# axiom_beta_sensor_cmv12000_v0_14_tht_d1d.net
KiCad netlist of a schematic drawn in EAGLE
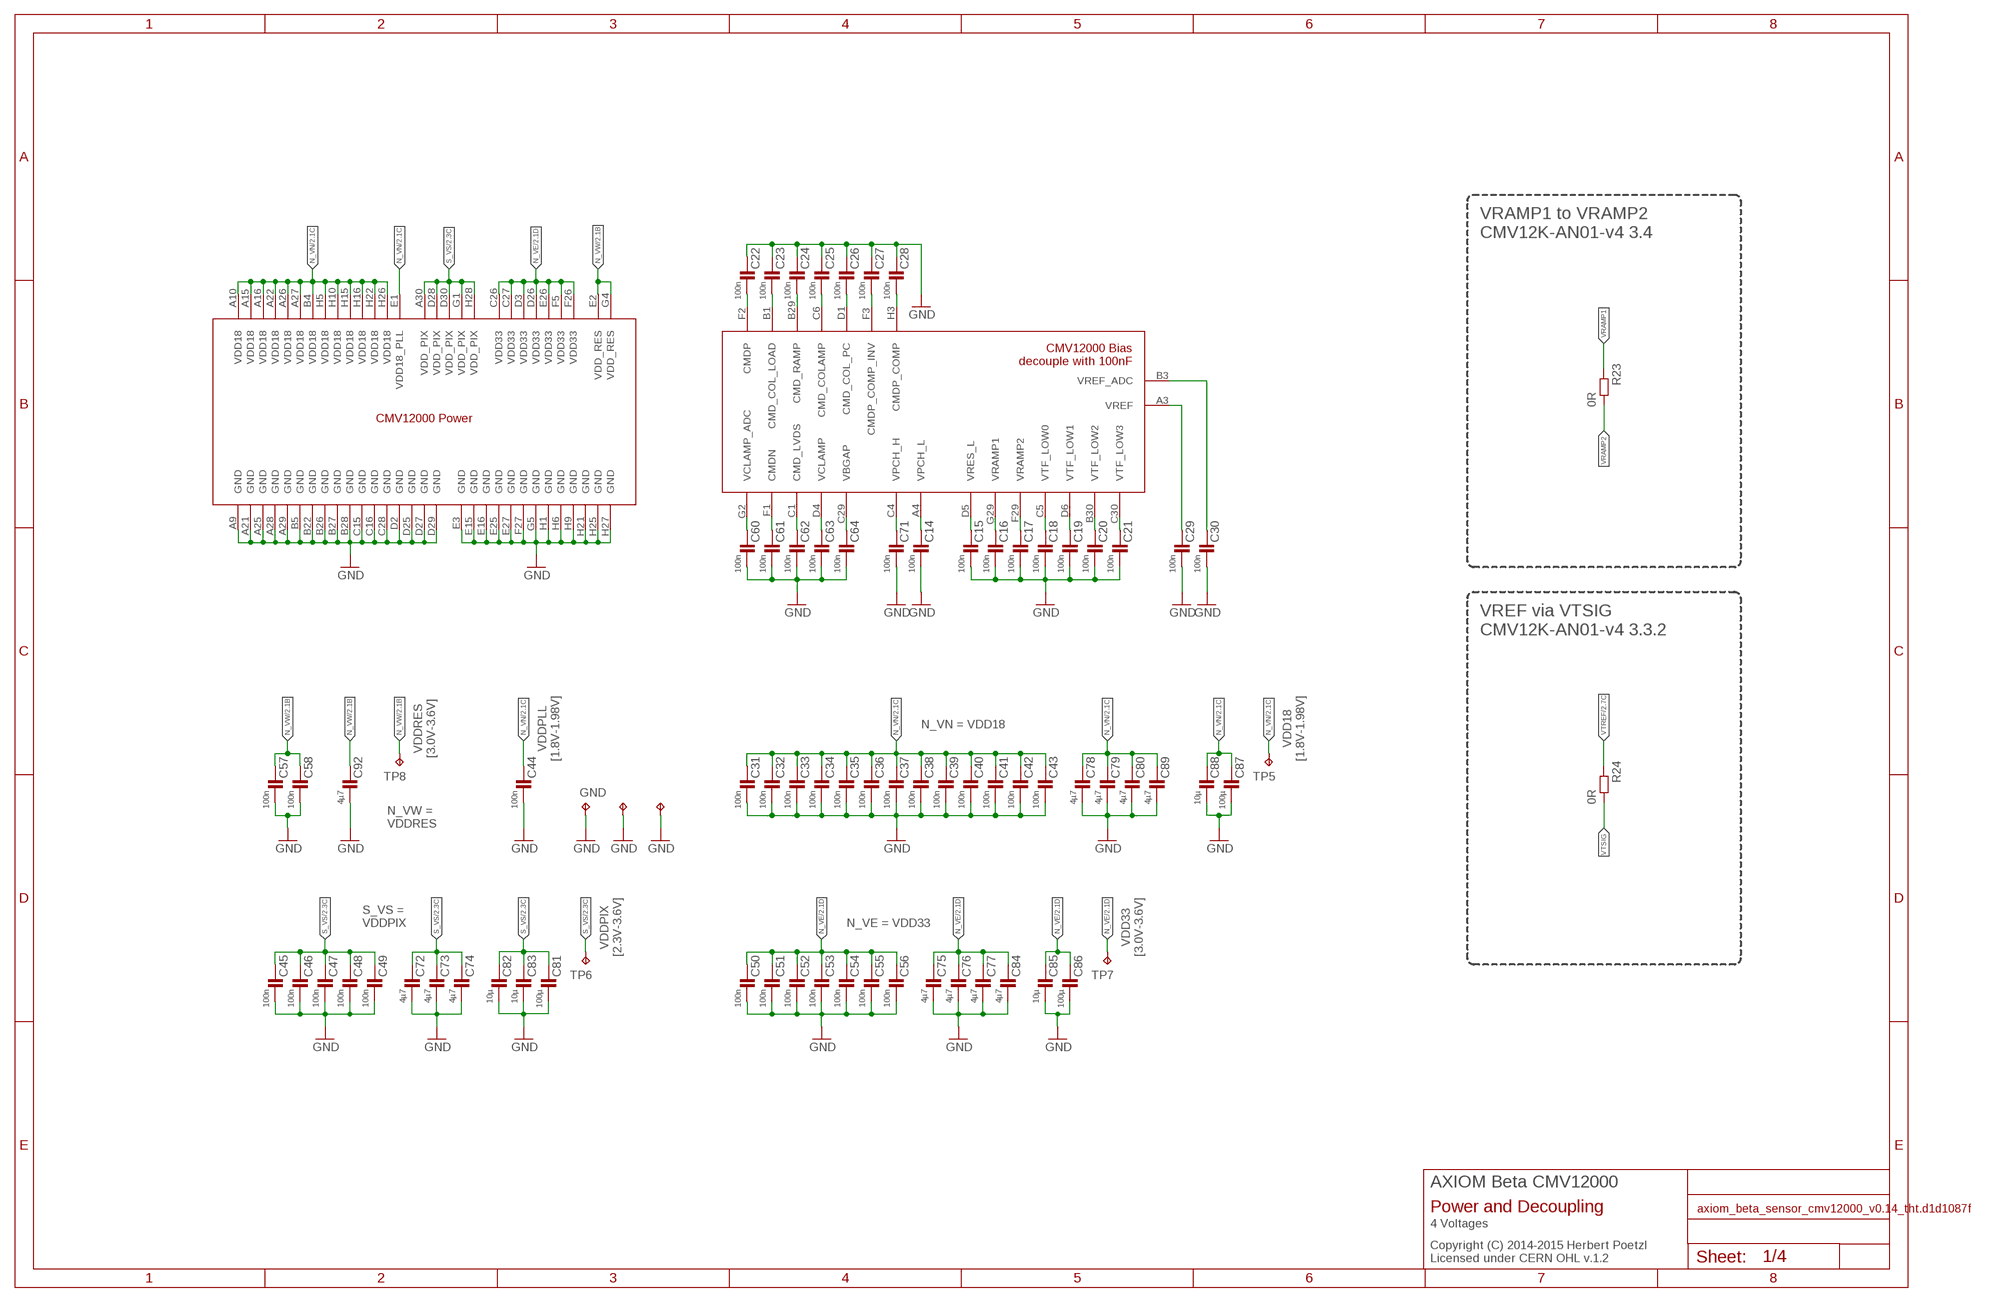
[diagram p0: schematic, sheet 1]
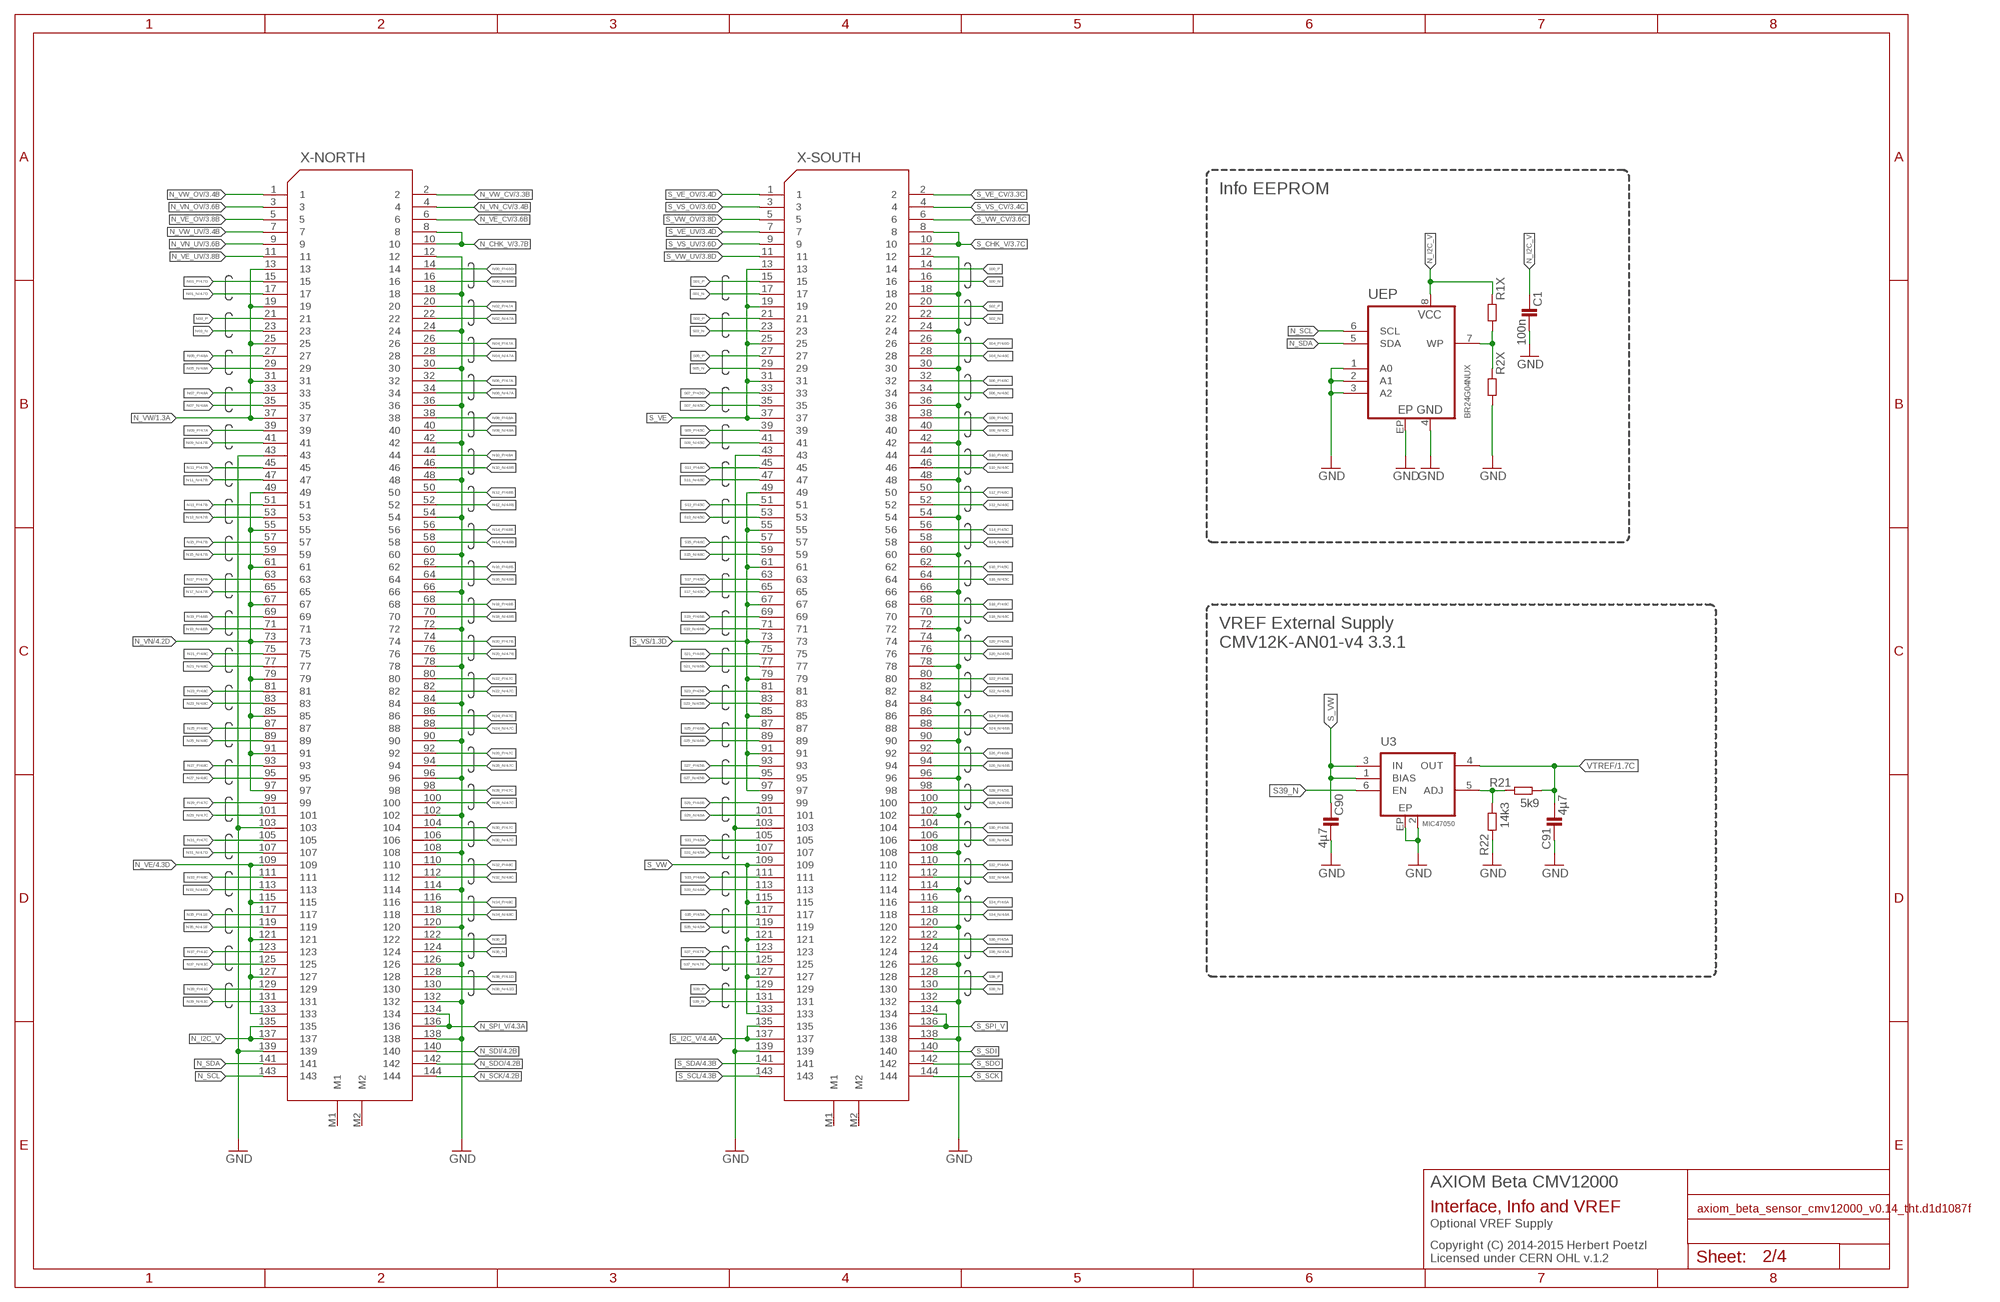
[diagram p1: schematic, sheet 2]
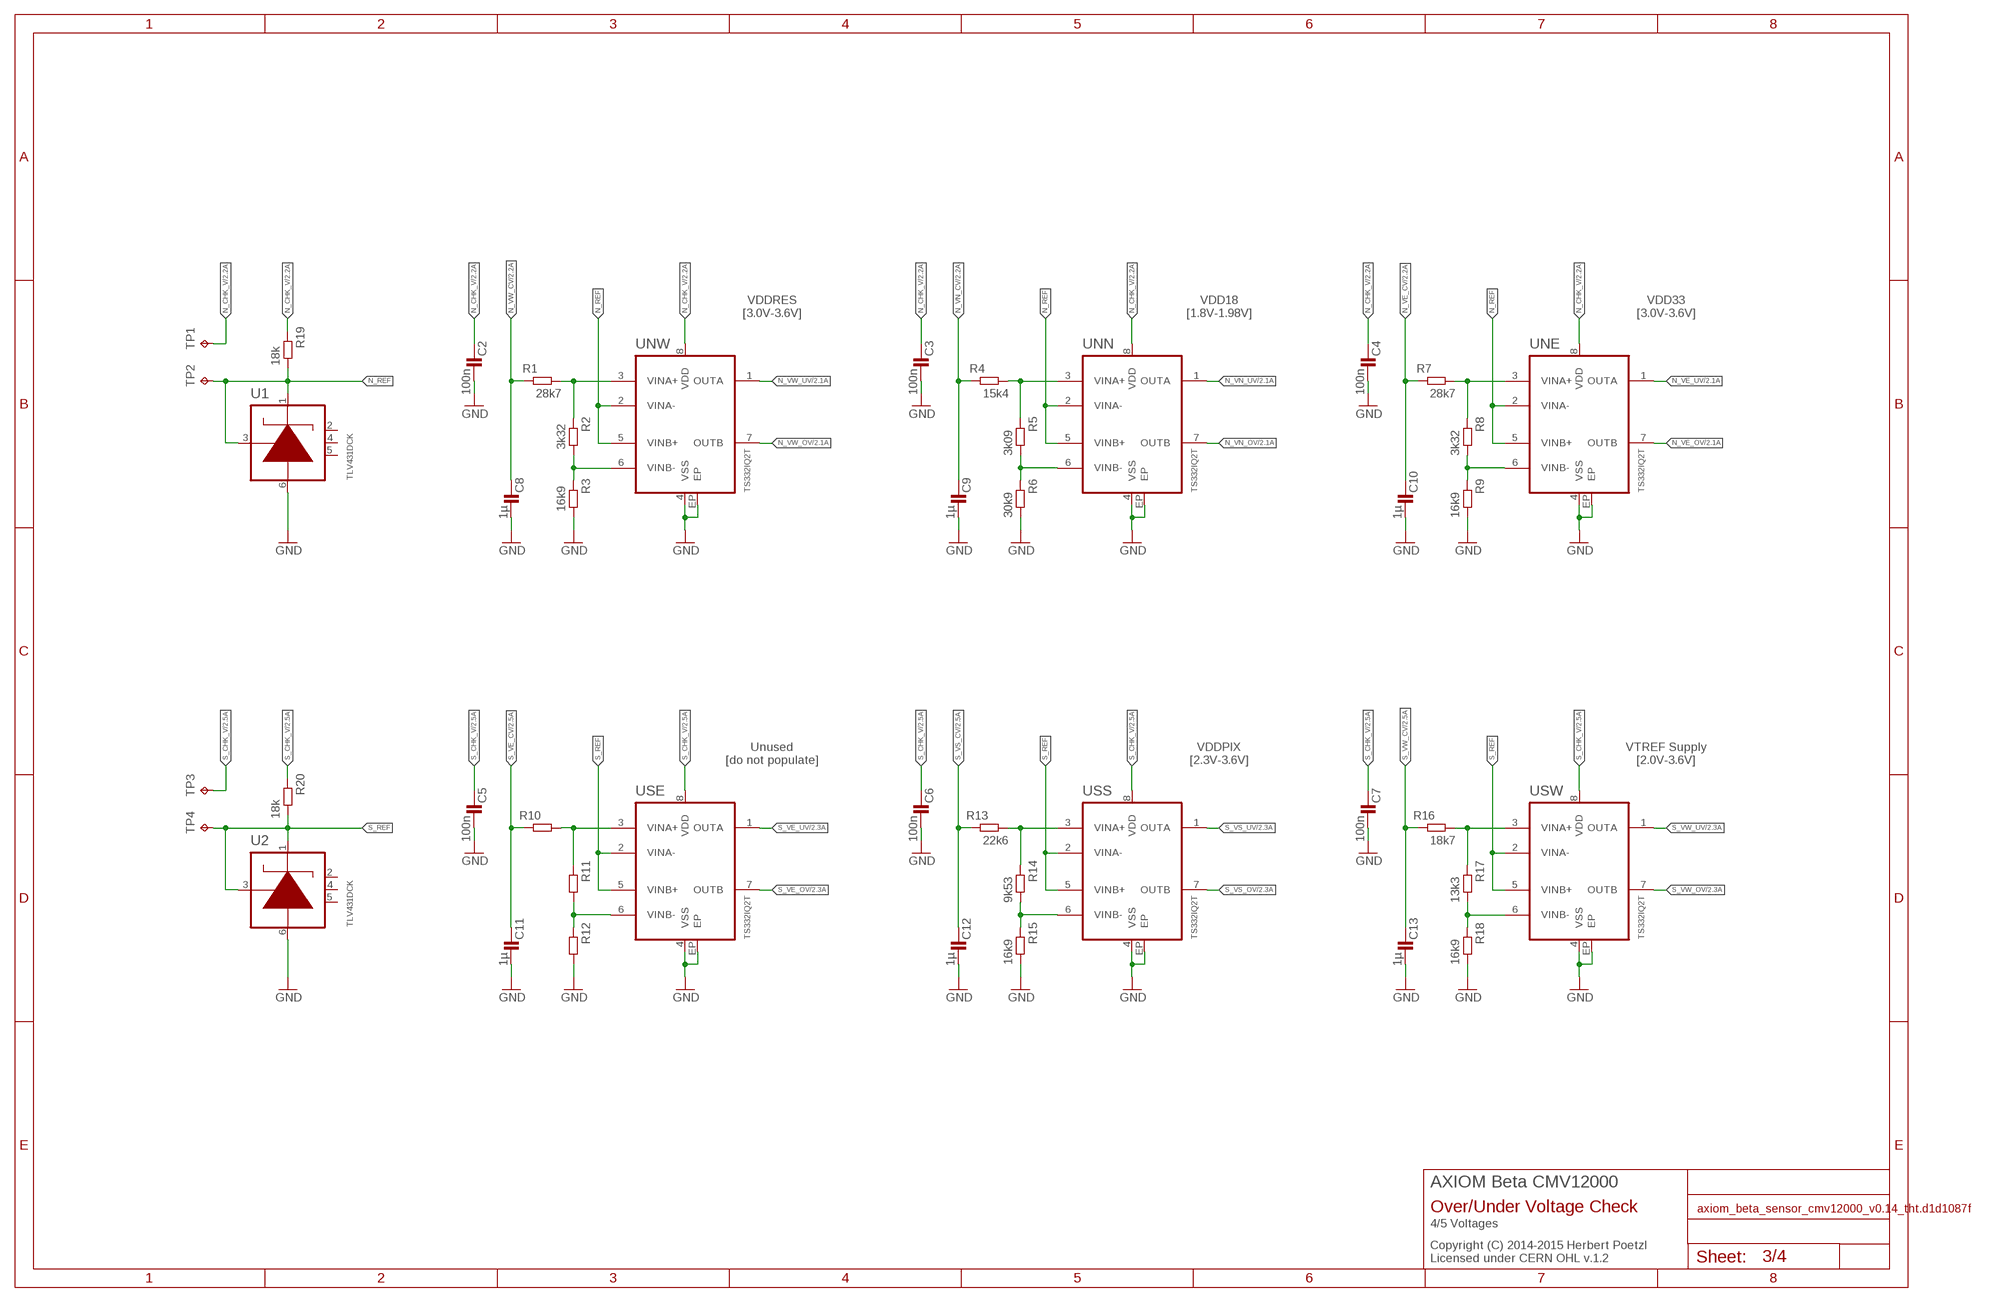
[diagram p2: schematic, sheet 3]
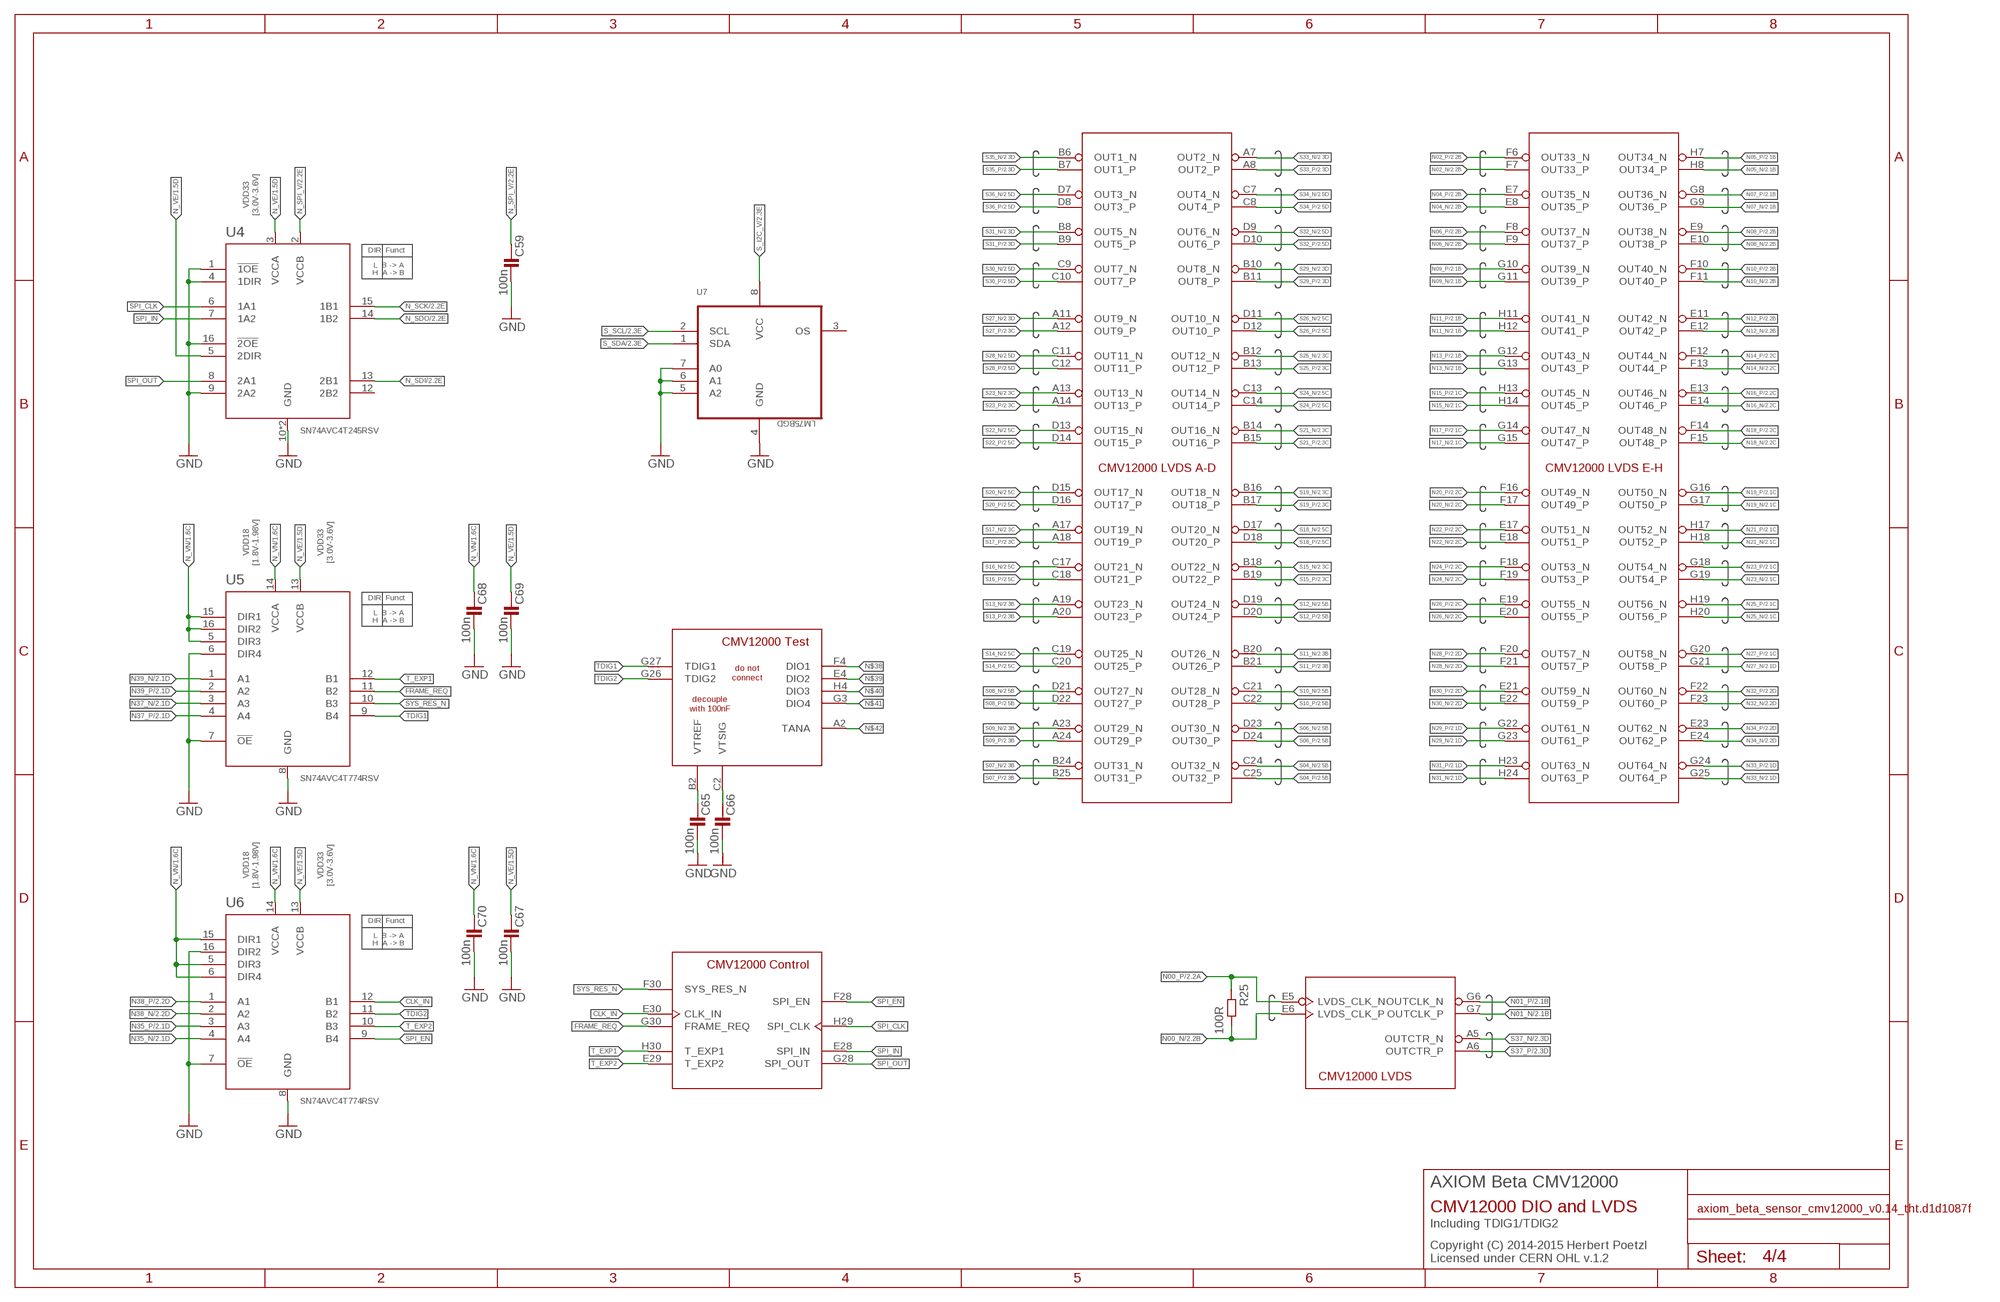
[diagram p3: schematic, sheet 4]

(export (version "E")
  (design (tool "Eeschema 10.0.6"))
  (components
    (comp (ref "C14")
      (value "100n")
      (footprint "eagle-import:0402-C")
      (libsource (lib "eagle-import") (part "C0402-C"))
    )
    (comp (ref "C15")
      (value "100n")
      (footprint "eagle-import:0402-C")
      (libsource (lib "eagle-import") (part "C0402-C"))
    )
    (comp (ref "C16")
      (value "100n")
      (footprint "eagle-import:0402-C")
      (libsource (lib "eagle-import") (part "C0402-C"))
    )
    (comp (ref "C17")
      (value "100n")
      (footprint "eagle-import:0402-C")
      (libsource (lib "eagle-import") (part "C0402-C"))
    )
    (comp (ref "C18")
      (value "100n")
      (footprint "eagle-import:0402-C")
      (libsource (lib "eagle-import") (part "C0402-C"))
    )
    (comp (ref "C19")
      (value "100n")
      (footprint "eagle-import:0402-C")
      (libsource (lib "eagle-import") (part "C0402-C"))
    )
    (comp (ref "C20")
      (value "100n")
      (footprint "eagle-import:0402-C")
      (libsource (lib "eagle-import") (part "C0402-C"))
    )
    (comp (ref "C21")
      (value "100n")
      (footprint "eagle-import:0402-C")
      (libsource (lib "eagle-import") (part "C0402-C"))
    )
    (comp (ref "C22")
      (value "100n")
      (footprint "eagle-import:0402-C")
      (libsource (lib "eagle-import") (part "C0402-C"))
    )
    (comp (ref "C23")
      (value "100n")
      (footprint "eagle-import:0402-C")
      (libsource (lib "eagle-import") (part "C0402-C"))
    )
    (comp (ref "C24")
      (value "100n")
      (footprint "eagle-import:0402-C")
      (libsource (lib "eagle-import") (part "C0402-C"))
    )
    (comp (ref "C25")
      (value "100n")
      (footprint "eagle-import:0402-C")
      (libsource (lib "eagle-import") (part "C0402-C"))
    )
    (comp (ref "C26")
      (value "100n")
      (footprint "eagle-import:0402-C")
      (libsource (lib "eagle-import") (part "C0402-C"))
    )
    (comp (ref "C27")
      (value "100n")
      (footprint "eagle-import:0402-C")
      (libsource (lib "eagle-import") (part "C0402-C"))
    )
    (comp (ref "C28")
      (value "100n")
      (footprint "eagle-import:0402-C")
      (libsource (lib "eagle-import") (part "C0402-C"))
    )
    (comp (ref "C29")
      (value "100n")
      (footprint "eagle-import:0402-C")
      (libsource (lib "eagle-import") (part "C0402-C"))
    )
    (comp (ref "C30")
      (value "100n")
      (footprint "eagle-import:0402-C")
      (libsource (lib "eagle-import") (part "C0402-C"))
    )
    (comp (ref "C31")
      (value "100n")
      (footprint "eagle-import:0402-C")
      (libsource (lib "eagle-import") (part "C0402-C"))
    )
    (comp (ref "C32")
      (value "100n")
      (footprint "eagle-import:0402-C")
      (libsource (lib "eagle-import") (part "C0402-C"))
    )
    (comp (ref "C33")
      (value "100n")
      (footprint "eagle-import:0402-C")
      (libsource (lib "eagle-import") (part "C0402-C"))
    )
    (comp (ref "C34")
      (value "100n")
      (footprint "eagle-import:0402-C")
      (libsource (lib "eagle-import") (part "C0402-C"))
    )
    (comp (ref "C35")
      (value "100n")
      (footprint "eagle-import:0402-C")
      (libsource (lib "eagle-import") (part "C0402-C"))
    )
    (comp (ref "C36")
      (value "100n")
      (footprint "eagle-import:0402-C")
      (libsource (lib "eagle-import") (part "C0402-C"))
    )
    (comp (ref "C37")
      (value "100n")
      (footprint "eagle-import:0402-C")
      (libsource (lib "eagle-import") (part "C0402-C"))
    )
    (comp (ref "C38")
      (value "100n")
      (footprint "eagle-import:0402-C")
      (libsource (lib "eagle-import") (part "C0402-C"))
    )
    (comp (ref "C39")
      (value "100n")
      (footprint "eagle-import:0402-C")
      (libsource (lib "eagle-import") (part "C0402-C"))
    )
    (comp (ref "C40")
      (value "100n")
      (footprint "eagle-import:0402-C")
      (libsource (lib "eagle-import") (part "C0402-C"))
    )
    (comp (ref "C41")
      (value "100n")
      (footprint "eagle-import:0402-C")
      (libsource (lib "eagle-import") (part "C0402-C"))
    )
    (comp (ref "C42")
      (value "100n")
      (footprint "eagle-import:0402-C")
      (libsource (lib "eagle-import") (part "C0402-C"))
    )
    (comp (ref "C43")
      (value "100n")
      (footprint "eagle-import:0402-C")
      (libsource (lib "eagle-import") (part "C0402-C"))
    )
    (comp (ref "C44")
      (value "100n")
      (footprint "eagle-import:0402-C")
      (libsource (lib "eagle-import") (part "C0402-C"))
    )
    (comp (ref "C45")
      (value "100n")
      (footprint "eagle-import:0402-C")
      (libsource (lib "eagle-import") (part "C0402-C"))
    )
    (comp (ref "C46")
      (value "100n")
      (footprint "eagle-import:0402-C")
      (libsource (lib "eagle-import") (part "C0402-C"))
    )
    (comp (ref "C47")
      (value "100n")
      (footprint "eagle-import:0402-C")
      (libsource (lib "eagle-import") (part "C0402-C"))
    )
    (comp (ref "C48")
      (value "100n")
      (footprint "eagle-import:0402-C")
      (libsource (lib "eagle-import") (part "C0402-C"))
    )
    (comp (ref "C49")
      (value "100n")
      (footprint "eagle-import:0402-C")
      (libsource (lib "eagle-import") (part "C0402-C"))
    )
    (comp (ref "C50")
      (value "100n")
      (footprint "eagle-import:0402-C")
      (libsource (lib "eagle-import") (part "C0402-C"))
    )
    (comp (ref "C51")
      (value "100n")
      (footprint "eagle-import:0402-C")
      (libsource (lib "eagle-import") (part "C0402-C"))
    )
    (comp (ref "C52")
      (value "100n")
      (footprint "eagle-import:0402-C")
      (libsource (lib "eagle-import") (part "C0402-C"))
    )
    (comp (ref "C53")
      (value "100n")
      (footprint "eagle-import:0402-C")
      (libsource (lib "eagle-import") (part "C0402-C"))
    )
    (comp (ref "C54")
      (value "100n")
      (footprint "eagle-import:0402-C")
      (libsource (lib "eagle-import") (part "C0402-C"))
    )
    (comp (ref "C55")
      (value "100n")
      (footprint "eagle-import:0402-C")
      (libsource (lib "eagle-import") (part "C0402-C"))
    )
    (comp (ref "C56")
      (value "100n")
      (footprint "eagle-import:0402-C")
      (libsource (lib "eagle-import") (part "C0402-C"))
    )
    (comp (ref "C57")
      (value "100n")
      (footprint "eagle-import:0402-C")
      (libsource (lib "eagle-import") (part "C0402-C"))
    )
    (comp (ref "C58")
      (value "100n")
      (footprint "eagle-import:0402-C")
      (libsource (lib "eagle-import") (part "C0402-C"))
    )
    (comp (ref "C60")
      (value "100n")
      (footprint "eagle-import:0402-C")
      (libsource (lib "eagle-import") (part "C0402-C"))
    )
    (comp (ref "C61")
      (value "100n")
      (footprint "eagle-import:0402-C")
      (libsource (lib "eagle-import") (part "C0402-C"))
    )
    (comp (ref "C62")
      (value "100n")
      (footprint "eagle-import:0402-C")
      (libsource (lib "eagle-import") (part "C0402-C"))
    )
    (comp (ref "C63")
      (value "100n")
      (footprint "eagle-import:0402-C")
      (libsource (lib "eagle-import") (part "C0402-C"))
    )
    (comp (ref "C64")
      (value "100n")
      (footprint "eagle-import:0402-C")
      (libsource (lib "eagle-import") (part "C0402-C"))
    )
    (comp (ref "C71")
      (value "100n")
      (footprint "eagle-import:0402-C")
      (libsource (lib "eagle-import") (part "C0402-C"))
    )
    (comp (ref "C72")
      (value "4µ7")
      (footprint "eagle-import:0402-B")
      (libsource (lib "eagle-import") (part "C0402-B"))
    )
    (comp (ref "C73")
      (value "4µ7")
      (footprint "eagle-import:0402-C")
      (libsource (lib "eagle-import") (part "C0402-C"))
    )
    (comp (ref "C74")
      (value "4µ7")
      (footprint "eagle-import:0402-C")
      (libsource (lib "eagle-import") (part "C0402-C"))
    )
    (comp (ref "C75")
      (value "4µ7")
      (footprint "eagle-import:0402-C")
      (libsource (lib "eagle-import") (part "C0402-C"))
    )
    (comp (ref "C76")
      (value "4µ7")
      (footprint "eagle-import:0402-C")
      (libsource (lib "eagle-import") (part "C0402-C"))
    )
    (comp (ref "C77")
      (value "4µ7")
      (footprint "eagle-import:0402-B")
      (libsource (lib "eagle-import") (part "C0402-B"))
    )
    (comp (ref "C78")
      (value "4µ7")
      (footprint "eagle-import:0402-B")
      (libsource (lib "eagle-import") (part "C0402-B"))
    )
    (comp (ref "C79")
      (value "4µ7")
      (footprint "eagle-import:0402-C")
      (libsource (lib "eagle-import") (part "C0402-C"))
    )
    (comp (ref "C80")
      (value "4µ7")
      (footprint "eagle-import:0402-C")
      (libsource (lib "eagle-import") (part "C0402-C"))
    )
    (comp (ref "C81")
      (value "100µ")
      (footprint "eagle-import:1206-B")
      (libsource (lib "eagle-import") (part "C1206-B"))
    )
    (comp (ref "C82")
      (value "10µ")
      (footprint "eagle-import:0603-C")
      (libsource (lib "eagle-import") (part "C0603-C"))
    )
    (comp (ref "C83")
      (value "10µ")
      (footprint "eagle-import:0603-C")
      (libsource (lib "eagle-import") (part "C0603-C"))
    )
    (comp (ref "C84")
      (value "4µ7")
      (footprint "eagle-import:0402-C")
      (libsource (lib "eagle-import") (part "C0402-C"))
    )
    (comp (ref "C85")
      (value "10µ")
      (footprint "eagle-import:0603-C")
      (libsource (lib "eagle-import") (part "C0603-C"))
    )
    (comp (ref "C86")
      (value "100µ")
      (footprint "eagle-import:1206-B")
      (libsource (lib "eagle-import") (part "C1206-B"))
    )
    (comp (ref "C87")
      (value "100µ")
      (footprint "eagle-import:1206-B")
      (libsource (lib "eagle-import") (part "C1206-B"))
    )
    (comp (ref "C88")
      (value "10µ")
      (footprint "eagle-import:0603-C")
      (libsource (lib "eagle-import") (part "C0603-C"))
    )
    (comp (ref "C89")
      (value "4µ7")
      (footprint "eagle-import:0402-C")
      (libsource (lib "eagle-import") (part "C0402-C"))
    )
    (comp (ref "C92")
      (value "4µ7")
      (footprint "eagle-import:0402-C")
      (libsource (lib "eagle-import") (part "C0402-C"))
    )
    (comp (ref "GND")
      (value "TPTP10R")
      (footprint "eagle-import:TP10R")
      (libsource (lib "eagle-import") (part "TPTP10R"))
    )
    (comp (ref "GND75")
      (value "TPTP10R")
      (footprint "eagle-import:TP10R")
      (libsource (lib "eagle-import") (part "TPTP10R"))
    )
    (comp (ref "GND77")
      (value "TPTP10R")
      (footprint "eagle-import:TP10R")
      (libsource (lib "eagle-import") (part "TPTP10R"))
    )
    (comp (ref "R23")
      (value "0R")
      (footprint "eagle-import:0402-C")
      (libsource (lib "eagle-import") (part "R0402-C"))
    )
    (comp (ref "R24")
      (value "0R")
      (footprint "eagle-import:0402-C")
      (libsource (lib "eagle-import") (part "R0402-C"))
    )
    (comp (ref "SENSOR")
      (value "CMV12000ANDON")
      (footprint "eagle-import:10-30-07-237-400T4")
      (libsource (lib "eagle-import") (part "CMV12000ANDON"))
    )
    (comp (ref "TP5")
      (value "TPTP10R")
      (footprint "eagle-import:TP10R")
      (libsource (lib "eagle-import") (part "TPTP10R"))
    )
    (comp (ref "TP6")
      (value "TPTP10R")
      (footprint "eagle-import:TP10R")
      (libsource (lib "eagle-import") (part "TPTP10R"))
    )
    (comp (ref "TP7")
      (value "TPTP10R")
      (footprint "eagle-import:TP10R")
      (libsource (lib "eagle-import") (part "TPTP10R"))
    )
    (comp (ref "TP8")
      (value "TPTP10R")
      (footprint "eagle-import:TP10R")
      (libsource (lib "eagle-import") (part "TPTP10R"))
    )
    (comp (ref "C59")
      (value "100n")
      (footprint "eagle-import:0402-C")
      (libsource (lib "eagle-import") (part "C0402-C"))
    )
    (comp (ref "C65")
      (value "100n")
      (footprint "eagle-import:0402-C")
      (libsource (lib "eagle-import") (part "C0402-C"))
    )
    (comp (ref "C66")
      (value "100n")
      (footprint "eagle-import:0402-C")
      (libsource (lib "eagle-import") (part "C0402-C"))
    )
    (comp (ref "C67")
      (value "100n")
      (footprint "eagle-import:0402-C")
      (libsource (lib "eagle-import") (part "C0402-C"))
    )
    (comp (ref "C68")
      (value "100n")
      (footprint "eagle-import:0402-C")
      (libsource (lib "eagle-import") (part "C0402-C"))
    )
    (comp (ref "C69")
      (value "100n")
      (footprint "eagle-import:0402-C")
      (libsource (lib "eagle-import") (part "C0402-C"))
    )
    (comp (ref "C70")
      (value "100n")
      (footprint "eagle-import:0402-C")
      (libsource (lib "eagle-import") (part "C0402-C"))
    )
    (comp (ref "R25")
      (value "100R")
      (footprint "eagle-import:0402-C")
      (libsource (lib "eagle-import") (part "R0402-C"))
    )
    (comp (ref "U4")
      (value "SN74AVC4T245RSV")
      (footprint "eagle-import:QFN40P185X265X55-16N")
      (libsource (lib "eagle-import") (part "SN74AVC4T245RSV"))
    )
    (comp (ref "U5")
      (value "SN74AVC4T774RSV")
      (footprint "eagle-import:QFN40P185X265X55-16N")
      (libsource (lib "eagle-import") (part "SN74AVC4T774RSV"))
    )
    (comp (ref "U6")
      (value "SN74AVC4T774RSV")
      (footprint "eagle-import:QFN40P185X265X55-16N")
      (libsource (lib "eagle-import") (part "SN74AVC4T774RSV"))
    )
    (comp (ref "U7")
      (value "LM75BGD")
      (footprint "eagle-import:SOT996-2_3")
      (libsource (lib "eagle-import") (part "LM75BGD"))
    )
    (comp (ref "C1")
      (value "100n")
      (footprint "eagle-import:0402-C")
      (libsource (lib "eagle-import") (part "C0402-C"))
    )
    (comp (ref "C90")
      (value "4µ7")
      (footprint "eagle-import:0402-C")
      (libsource (lib "eagle-import") (part "C0402-C"))
    )
    (comp (ref "C91")
      (value "4µ7")
      (footprint "eagle-import:0402-C")
      (libsource (lib "eagle-import") (part "C0402-C"))
    )
    (comp (ref "R1X")
      (value "R0402-C")
      (footprint "eagle-import:0402-C")
      (libsource (lib "eagle-import") (part "R0402-C"))
    )
    (comp (ref "R2X")
      (value "R0402-C")
      (footprint "eagle-import:0402-C")
      (libsource (lib "eagle-import") (part "R0402-C"))
    )
    (comp (ref "R21")
      (value "5k9")
      (footprint "eagle-import:0402-C")
      (libsource (lib "eagle-import") (part "R0402-C"))
    )
    (comp (ref "R22")
      (value "14k3")
      (footprint "eagle-import:0402-C")
      (libsource (lib "eagle-import") (part "R0402-C"))
    )
    (comp (ref "U3")
      (value "MIC47050")
      (footprint "eagle-import:MLF-6")
      (libsource (lib "eagle-import") (part "MIC47050-ADJ"))
    )
    (comp (ref "UEP")
      (value "BR24G04NUX")
      (footprint "eagle-import:DFN200X300X100-9N")
      (libsource (lib "eagle-import") (part "BR24G04NUX"))
    )
    (comp (ref "X-NORTH")
      (value "FX10-144P")
      (footprint "eagle-import:FX10A-144P")
      (libsource (lib "eagle-import") (part "FX10-144P"))
    )
    (comp (ref "X-SOUTH")
      (value "FX10-144P")
      (footprint "eagle-import:FX10A-144P")
      (libsource (lib "eagle-import") (part "FX10-144P"))
    )
    (comp (ref "C2")
      (value "100n")
      (footprint "eagle-import:0402-C")
      (libsource (lib "eagle-import") (part "C0402-C"))
    )
    (comp (ref "C3")
      (value "100n")
      (footprint "eagle-import:0402-C")
      (libsource (lib "eagle-import") (part "C0402-C"))
    )
    (comp (ref "C4")
      (value "100n")
      (footprint "eagle-import:0402-C")
      (libsource (lib "eagle-import") (part "C0402-C"))
    )
    (comp (ref "C5")
      (value "100n")
      (footprint "eagle-import:0402-C")
      (libsource (lib "eagle-import") (part "C0402-C"))
    )
    (comp (ref "C6")
      (value "100n")
      (footprint "eagle-import:0402-C")
      (libsource (lib "eagle-import") (part "C0402-C"))
    )
    (comp (ref "C7")
      (value "100n")
      (footprint "eagle-import:0402-C")
      (libsource (lib "eagle-import") (part "C0402-C"))
    )
    (comp (ref "C8")
      (value "1µ")
      (footprint "eagle-import:0402-C")
      (libsource (lib "eagle-import") (part "C0402-C"))
    )
    (comp (ref "C9")
      (value "1µ")
      (footprint "eagle-import:0402-C")
      (libsource (lib "eagle-import") (part "C0402-C"))
    )
    (comp (ref "C10")
      (value "1µ")
      (footprint "eagle-import:0402-C")
      (libsource (lib "eagle-import") (part "C0402-C"))
    )
    (comp (ref "C11")
      (value "1µ")
      (footprint "eagle-import:0402-C")
      (libsource (lib "eagle-import") (part "C0402-C"))
    )
    (comp (ref "C12")
      (value "1µ")
      (footprint "eagle-import:0402-C")
      (libsource (lib "eagle-import") (part "C0402-C"))
    )
    (comp (ref "C13")
      (value "1µ")
      (footprint "eagle-import:0402-C")
      (libsource (lib "eagle-import") (part "C0402-C"))
    )
    (comp (ref "R1")
      (value "28k7")
      (footprint "eagle-import:0402-C")
      (libsource (lib "eagle-import") (part "R0402-C"))
    )
    (comp (ref "R2")
      (value "3k32")
      (footprint "eagle-import:0402-C")
      (libsource (lib "eagle-import") (part "R0402-C"))
    )
    (comp (ref "R3")
      (value "16k9")
      (footprint "eagle-import:0402-C")
      (libsource (lib "eagle-import") (part "R0402-C"))
    )
    (comp (ref "R4")
      (value "15k4")
      (footprint "eagle-import:0402-C")
      (libsource (lib "eagle-import") (part "R0402-C"))
    )
    (comp (ref "R5")
      (value "3k09")
      (footprint "eagle-import:0402-C")
      (libsource (lib "eagle-import") (part "R0402-C"))
    )
    (comp (ref "R6")
      (value "30k9")
      (footprint "eagle-import:0402-C")
      (libsource (lib "eagle-import") (part "R0402-C"))
    )
    (comp (ref "R7")
      (value "28k7")
      (footprint "eagle-import:0402-C")
      (libsource (lib "eagle-import") (part "R0402-C"))
    )
    (comp (ref "R8")
      (value "3k32")
      (footprint "eagle-import:0402-C")
      (libsource (lib "eagle-import") (part "R0402-C"))
    )
    (comp (ref "R9")
      (value "16k9")
      (footprint "eagle-import:0402-C")
      (libsource (lib "eagle-import") (part "R0402-C"))
    )
    (comp (ref "R10")
      (value "R0402-C")
      (footprint "eagle-import:0402-C")
      (libsource (lib "eagle-import") (part "R0402-C"))
    )
    (comp (ref "R11")
      (value "R0402-C")
      (footprint "eagle-import:0402-C")
      (libsource (lib "eagle-import") (part "R0402-C"))
    )
    (comp (ref "R12")
      (value "R0402-C")
      (footprint "eagle-import:0402-C")
      (libsource (lib "eagle-import") (part "R0402-C"))
    )
    (comp (ref "R13")
      (value "22k6")
      (footprint "eagle-import:0402-C")
      (libsource (lib "eagle-import") (part "R0402-C"))
    )
    (comp (ref "R14")
      (value "9k53")
      (footprint "eagle-import:0402-C")
      (libsource (lib "eagle-import") (part "R0402-C"))
    )
    (comp (ref "R15")
      (value "16k9")
      (footprint "eagle-import:0402-C")
      (libsource (lib "eagle-import") (part "R0402-C"))
    )
    (comp (ref "R16")
      (value "18k7")
      (footprint "eagle-import:0402-C")
      (libsource (lib "eagle-import") (part "R0402-C"))
    )
    (comp (ref "R17")
      (value "13k3")
      (footprint "eagle-import:0402-C")
      (libsource (lib "eagle-import") (part "R0402-C"))
    )
    (comp (ref "R18")
      (value "16k9")
      (footprint "eagle-import:0402-C")
      (libsource (lib "eagle-import") (part "R0402-C"))
    )
    (comp (ref "R19")
      (value "18k")
      (footprint "eagle-import:0402-C")
      (libsource (lib "eagle-import") (part "R0402-C"))
    )
    (comp (ref "R20")
      (value "18k")
      (footprint "eagle-import:0402-C")
      (libsource (lib "eagle-import") (part "R0402-C"))
    )
    (comp (ref "TP1")
      (value "TPTP10R")
      (footprint "eagle-import:TP10R")
      (libsource (lib "eagle-import") (part "TPTP10R"))
    )
    (comp (ref "TP2")
      (value "TPTP10R")
      (footprint "eagle-import:TP10R")
      (libsource (lib "eagle-import") (part "TPTP10R"))
    )
    (comp (ref "TP3")
      (value "TPTP10R")
      (footprint "eagle-import:TP10R")
      (libsource (lib "eagle-import") (part "TPTP10R"))
    )
    (comp (ref "TP4")
      (value "TPTP10R")
      (footprint "eagle-import:TP10R")
      (libsource (lib "eagle-import") (part "TPTP10R"))
    )
    (comp (ref "U1")
      (value "TLV431DCK")
      (footprint "eagle-import:SOT65P210X110-6N")
      (libsource (lib "eagle-import") (part "TLV431DCK"))
    )
    (comp (ref "U2")
      (value "TLV431DCK")
      (footprint "eagle-import:SOT65P210X110-6N")
      (libsource (lib "eagle-import") (part "TLV431DCK"))
    )
    (comp (ref "UNE")
      (value "TS332IQ2T")
      (footprint "eagle-import:DFN200X200X100-9N")
      (libsource (lib "eagle-import") (part "TS332IQ2T"))
    )
    (comp (ref "UNN")
      (value "TS332IQ2T")
      (footprint "eagle-import:DFN200X200X100-9N")
      (libsource (lib "eagle-import") (part "TS332IQ2T"))
    )
    (comp (ref "UNW")
      (value "TS332IQ2T")
      (footprint "eagle-import:DFN200X200X100-9N")
      (libsource (lib "eagle-import") (part "TS332IQ2T"))
    )
    (comp (ref "USE")
      (value "TS332IQ2T")
      (footprint "eagle-import:DFN200X200X100-9N")
      (libsource (lib "eagle-import") (part "TS332IQ2T"))
    )
    (comp (ref "USS")
      (value "TS332IQ2T")
      (footprint "eagle-import:DFN200X200X100-9N")
      (libsource (lib "eagle-import") (part "TS332IQ2T"))
    )
    (comp (ref "USW")
      (value "TS332IQ2T")
      (footprint "eagle-import:DFN200X200X100-9N")
      (libsource (lib "eagle-import") (part "TS332IQ2T"))
    )
  )
  (nets
    (net (code "1") (name "CLK_IN") (class "Default")
      (node (ref "SENSOR") (pin "E30") (pinfunction "CLK_IN_E30") (pintype "input"))
      (node (ref "U6") (pin "12") (pinfunction "B1_12") (pintype "bidirectional"))
    )
    (net (code "2") (name "FRAME_REQ") (class "Default")
      (node (ref "SENSOR") (pin "G30") (pinfunction "FRAME_REQ_G30") (pintype "input"))
      (node (ref "U5") (pin "11") (pinfunction "B2_11") (pintype "bidirectional"))
    )
    (net (code "3") (name "GND") (class "Default")
      (node (ref "C1") (pin "2") (pinfunction "2_2") (pintype "passive"))
      (node (ref "C10") (pin "2") (pinfunction "2_2") (pintype "passive"))
      (node (ref "C11") (pin "2") (pinfunction "2_2") (pintype "passive"))
      (node (ref "C12") (pin "2") (pinfunction "2_2") (pintype "passive"))
      (node (ref "C13") (pin "2") (pinfunction "2_2") (pintype "passive"))
      (node (ref "C14") (pin "2") (pinfunction "2_2") (pintype "passive"))
      (node (ref "C15") (pin "2") (pinfunction "2_2") (pintype "passive"))
      (node (ref "C16") (pin "2") (pinfunction "2_2") (pintype "passive"))
      (node (ref "C17") (pin "2") (pinfunction "2_2") (pintype "passive"))
      (node (ref "C18") (pin "2") (pinfunction "2_2") (pintype "passive"))
      (node (ref "C19") (pin "2") (pinfunction "2_2") (pintype "passive"))
      (node (ref "C2") (pin "2") (pinfunction "2_2") (pintype "passive"))
      (node (ref "C20") (pin "2") (pinfunction "2_2") (pintype "passive"))
      (node (ref "C21") (pin "2") (pinfunction "2_2") (pintype "passive"))
      (node (ref "C22") (pin "1") (pinfunction "1_1") (pintype "passive"))
      (node (ref "C23") (pin "1") (pinfunction "1_1") (pintype "passive"))
      (node (ref "C24") (pin "1") (pinfunction "1_1") (pintype "passive"))
      (node (ref "C25") (pin "1") (pinfunction "1_1") (pintype "passive"))
      (node (ref "C26") (pin "1") (pinfunction "1_1") (pintype "passive"))
      (node (ref "C27") (pin "1") (pinfunction "1_1") (pintype "passive"))
      (node (ref "C28") (pin "1") (pinfunction "1_1") (pintype "passive"))
      (node (ref "C29") (pin "2") (pinfunction "2_2") (pintype "passive"))
      (node (ref "C3") (pin "2") (pinfunction "2_2") (pintype "passive"))
      (node (ref "C30") (pin "2") (pinfunction "2_2") (pintype "passive"))
      (node (ref "C31") (pin "2") (pinfunction "2_2") (pintype "passive"))
      (node (ref "C32") (pin "2") (pinfunction "2_2") (pintype "passive"))
      (node (ref "C33") (pin "2") (pinfunction "2_2") (pintype "passive"))
      (node (ref "C34") (pin "2") (pinfunction "2_2") (pintype "passive"))
      (node (ref "C35") (pin "2") (pinfunction "2_2") (pintype "passive"))
      (node (ref "C36") (pin "2") (pinfunction "2_2") (pintype "passive"))
      (node (ref "C37") (pin "2") (pinfunction "2_2") (pintype "passive"))
      (node (ref "C38") (pin "2") (pinfunction "2_2") (pintype "passive"))
      (node (ref "C39") (pin "2") (pinfunction "2_2") (pintype "passive"))
      (node (ref "C4") (pin "2") (pinfunction "2_2") (pintype "passive"))
      (node (ref "C40") (pin "2") (pinfunction "2_2") (pintype "passive"))
      (node (ref "C41") (pin "2") (pinfunction "2_2") (pintype "passive"))
      (node (ref "C42") (pin "2") (pinfunction "2_2") (pintype "passive"))
      (node (ref "C43") (pin "2") (pinfunction "2_2") (pintype "passive"))
      (node (ref "C44") (pin "2") (pinfunction "2_2") (pintype "passive"))
      (node (ref "C45") (pin "2") (pinfunction "2_2") (pintype "passive"))
      (node (ref "C46") (pin "2") (pinfunction "2_2") (pintype "passive"))
      (node (ref "C47") (pin "2") (pinfunction "2_2") (pintype "passive"))
      (node (ref "C48") (pin "2") (pinfunction "2_2") (pintype "passive"))
      (node (ref "C49") (pin "2") (pinfunction "2_2") (pintype "passive"))
      (node (ref "C5") (pin "2") (pinfunction "2_2") (pintype "passive"))
      (node (ref "C50") (pin "2") (pinfunction "2_2") (pintype "passive"))
      (node (ref "C51") (pin "2") (pinfunction "2_2") (pintype "passive"))
      (node (ref "C52") (pin "2") (pinfunction "2_2") (pintype "passive"))
      (node (ref "C53") (pin "2") (pinfunction "2_2") (pintype "passive"))
      (node (ref "C54") (pin "2") (pinfunction "2_2") (pintype "passive"))
      (node (ref "C55") (pin "2") (pinfunction "2_2") (pintype "passive"))
      (node (ref "C56") (pin "2") (pinfunction "2_2") (pintype "passive"))
      (node (ref "C57") (pin "2") (pinfunction "2_2") (pintype "passive"))
      (node (ref "C58") (pin "2") (pinfunction "2_2") (pintype "passive"))
      (node (ref "C59") (pin "2") (pinfunction "2_2") (pintype "passive"))
      (node (ref "C6") (pin "2") (pinfunction "2_2") (pintype "passive"))
      (node (ref "C60") (pin "2") (pinfunction "2_2") (pintype "passive"))
      (node (ref "C61") (pin "2") (pinfunction "2_2") (pintype "passive"))
      (node (ref "C62") (pin "2") (pinfunction "2_2") (pintype "passive"))
      (node (ref "C63") (pin "2") (pinfunction "2_2") (pintype "passive"))
      (node (ref "C64") (pin "2") (pinfunction "2_2") (pintype "passive"))
      (node (ref "C65") (pin "2") (pinfunction "2_2") (pintype "passive"))
      (node (ref "C66") (pin "2") (pinfunction "2_2") (pintype "passive"))
      (node (ref "C67") (pin "2") (pinfunction "2_2") (pintype "passive"))
      (node (ref "C68") (pin "2") (pinfunction "2_2") (pintype "passive"))
      (node (ref "C69") (pin "2") (pinfunction "2_2") (pintype "passive"))
      (node (ref "C7") (pin "2") (pinfunction "2_2") (pintype "passive"))
      (node (ref "C70") (pin "2") (pinfunction "2_2") (pintype "passive"))
      (node (ref "C71") (pin "2") (pinfunction "2_2") (pintype "passive"))
      (node (ref "C72") (pin "2") (pinfunction "2_2") (pintype "passive"))
      (node (ref "C73") (pin "2") (pinfunction "2_2") (pintype "passive"))
      (node (ref "C74") (pin "2") (pinfunction "2_2") (pintype "passive"))
      (node (ref "C75") (pin "2") (pinfunction "2_2") (pintype "passive"))
      (node (ref "C76") (pin "2") (pinfunction "2_2") (pintype "passive"))
      (node (ref "C77") (pin "2") (pinfunction "2_2") (pintype "passive"))
      (node (ref "C78") (pin "2") (pinfunction "2_2") (pintype "passive"))
      (node (ref "C79") (pin "2") (pinfunction "2_2") (pintype "passive"))
      (node (ref "C8") (pin "2") (pinfunction "2_2") (pintype "passive"))
      (node (ref "C80") (pin "2") (pinfunction "2_2") (pintype "passive"))
      (node (ref "C81") (pin "2") (pinfunction "2_2") (pintype "passive"))
      (node (ref "C82") (pin "2") (pinfunction "2_2") (pintype "passive"))
      (node (ref "C83") (pin "2") (pinfunction "2_2") (pintype "passive"))
      (node (ref "C84") (pin "2") (pinfunction "2_2") (pintype "passive"))
      (node (ref "C85") (pin "2") (pinfunction "2_2") (pintype "passive"))
      (node (ref "C86") (pin "2") (pinfunction "2_2") (pintype "passive"))
      (node (ref "C87") (pin "2") (pinfunction "2_2") (pintype "passive"))
      (node (ref "C88") (pin "2") (pinfunction "2_2") (pintype "passive"))
      (node (ref "C89") (pin "2") (pinfunction "2_2") (pintype "passive"))
      (node (ref "C9") (pin "2") (pinfunction "2_2") (pintype "passive"))
      (node (ref "C90") (pin "2") (pinfunction "2_2") (pintype "passive"))
      (node (ref "C91") (pin "1") (pinfunction "1_1") (pintype "passive"))
      (node (ref "C92") (pin "2") (pinfunction "2_2") (pintype "passive"))
      (node (ref "GND") (pin "TP") (pinfunction "TP_TP") (pintype "input"))
      (node (ref "GND75") (pin "TP") (pinfunction "TP_TP") (pintype "input"))
      (node (ref "GND77") (pin "TP") (pinfunction "TP_TP") (pintype "input"))
      (node (ref "R12") (pin "2") (pinfunction "2_2") (pintype "passive"))
      (node (ref "R15") (pin "2") (pinfunction "2_2") (pintype "passive"))
      (node (ref "R18") (pin "2") (pinfunction "2_2") (pintype "passive"))
      (node (ref "R22") (pin "1") (pinfunction "1_1") (pintype "passive"))
      (node (ref "R2X") (pin "2") (pinfunction "2_2") (pintype "passive"))
      (node (ref "R3") (pin "2") (pinfunction "2_2") (pintype "passive"))
      (node (ref "R6") (pin "2") (pinfunction "2_2") (pintype "passive"))
      (node (ref "R9") (pin "2") (pinfunction "2_2") (pintype "passive"))
      (node (ref "SENSOR") (pin "A21") (pinfunction "GND_A21") (pintype "power_in"))
      (node (ref "SENSOR") (pin "A25") (pinfunction "GND_A25") (pintype "power_in"))
      (node (ref "SENSOR") (pin "A28") (pinfunction "GND_A28") (pintype "power_in"))
      (node (ref "SENSOR") (pin "A29") (pinfunction "GND_A29") (pintype "power_in"))
      (node (ref "SENSOR") (pin "A9") (pinfunction "GND_A9") (pintype "power_in"))
      (node (ref "SENSOR") (pin "B22") (pinfunction "GND_B22") (pintype "power_in"))
      (node (ref "SENSOR") (pin "B26") (pinfunction "GND_B26") (pintype "power_in"))
      (node (ref "SENSOR") (pin "B27") (pinfunction "GND_B27") (pintype "power_in"))
      (node (ref "SENSOR") (pin "B28") (pinfunction "GND_B28") (pintype "power_in"))
      (node (ref "SENSOR") (pin "B5") (pinfunction "GND_B5") (pintype "power_in"))
      (node (ref "SENSOR") (pin "C15") (pinfunction "GND_C15") (pintype "power_in"))
      (node (ref "SENSOR") (pin "C16") (pinfunction "GND_C16") (pintype "power_in"))
      (node (ref "SENSOR") (pin "C28") (pinfunction "GND_C28") (pintype "power_in"))
      (node (ref "SENSOR") (pin "D2") (pinfunction "GND_D2") (pintype "power_in"))
      (node (ref "SENSOR") (pin "D25") (pinfunction "GND_D25") (pintype "power_in"))
      (node (ref "SENSOR") (pin "D27") (pinfunction "GND_D27") (pintype "power_in"))
      (node (ref "SENSOR") (pin "D29") (pinfunction "GND_D29") (pintype "power_in"))
      (node (ref "SENSOR") (pin "E15") (pinfunction "GND_E15") (pintype "power_in"))
      (node (ref "SENSOR") (pin "E16") (pinfunction "GND_E16") (pintype "power_in"))
      (node (ref "SENSOR") (pin "E25") (pinfunction "GND_E25") (pintype "power_in"))
      (node (ref "SENSOR") (pin "E27") (pinfunction "GND_E27") (pintype "power_in"))
      (node (ref "SENSOR") (pin "E3") (pinfunction "GND_E3") (pintype "power_in"))
      (node (ref "SENSOR") (pin "F27") (pinfunction "GND_F27") (pintype "power_in"))
      (node (ref "SENSOR") (pin "G5") (pinfunction "GND_G5") (pintype "power_in"))
      (node (ref "SENSOR") (pin "H1") (pinfunction "GND_H1") (pintype "power_in"))
      (node (ref "SENSOR") (pin "H21") (pinfunction "GND_H21") (pintype "power_in"))
      (node (ref "SENSOR") (pin "H25") (pinfunction "GND_H25") (pintype "power_in"))
      (node (ref "SENSOR") (pin "H27") (pinfunction "GND_H27") (pintype "power_in"))
      (node (ref "SENSOR") (pin "H6") (pinfunction "GND_H6") (pintype "power_in"))
      (node (ref "SENSOR") (pin "H9") (pinfunction "GND_H9") (pintype "power_in"))
      (node (ref "U1") (pin "6") (pinfunction "ANODE_6") (pintype "input"))
      (node (ref "U2") (pin "6") (pinfunction "ANODE_6") (pintype "input"))
      (node (ref "U3") (pin "2") (pinfunction "GND_2") (pintype "power_in"))
      (node (ref "U3") (pin "EP") (pinfunction "EP_EP") (pintype "power_in"))
      (node (ref "U4") (pin "1") (pinfunction "~{1OE}_1") (pintype "input"))
      (node (ref "U4") (pin "10") (pinfunction "GND_10") (pintype "passive"))
      (node (ref "U4") (pin "11") (pinfunction "GND_11") (pintype "passive"))
      (node (ref "U4") (pin "16") (pinfunction "~{2OE}_16") (pintype "input"))
      (node (ref "U4") (pin "4") (pinfunction "1DIR_4") (pintype "input"))
      (node (ref "U4") (pin "9") (pinfunction "2A2_9") (pintype "output"))
      (node (ref "U5") (pin "6") (pinfunction "DIR4_6") (pintype "input"))
      (node (ref "U5") (pin "7") (pinfunction "~{OE}_7") (pintype "input"))
      (node (ref "U5") (pin "8") (pinfunction "GND_8") (pintype "passive"))
      (node (ref "U6") (pin "16") (pinfunction "DIR2_16") (pintype "input"))
      (node (ref "U6") (pin "7") (pinfunction "~{OE}_7") (pintype "input"))
      (node (ref "U6") (pin "8") (pinfunction "GND_8") (pintype "passive"))
      (node (ref "U7") (pin "4") (pinfunction "GND_4") (pintype "power_in"))
      (node (ref "U7") (pin "5") (pinfunction "A2_5") (pintype "input"))
      (node (ref "U7") (pin "6") (pinfunction "A1_6") (pintype "input"))
      (node (ref "U7") (pin "7") (pinfunction "A0_7") (pintype "input"))
      (node (ref "UEP") (pin "1") (pinfunction "A0_1") (pintype "input"))
      (node (ref "UEP") (pin "2") (pinfunction "A1_2") (pintype "input"))
      (node (ref "UEP") (pin "3") (pinfunction "A2_3") (pintype "input"))
      (node (ref "UEP") (pin "4") (pinfunction "GND_4") (pintype "passive"))
      (node (ref "UEP") (pin "EP") (pinfunction "EP_EP") (pintype "passive"))
      (node (ref "UNE") (pin "4") (pinfunction "VSS_4") (pintype "power_in"))
      (node (ref "UNE") (pin "EP") (pinfunction "EP_EP") (pintype "passive"))
      (node (ref "UNN") (pin "4") (pinfunction "VSS_4") (pintype "power_in"))
      (node (ref "UNN") (pin "EP") (pinfunction "EP_EP") (pintype "passive"))
      (node (ref "UNW") (pin "4") (pinfunction "VSS_4") (pintype "power_in"))
      (node (ref "UNW") (pin "EP") (pinfunction "EP_EP") (pintype "passive"))
      (node (ref "USE") (pin "4") (pinfunction "VSS_4") (pintype "power_in"))
      (node (ref "USE") (pin "EP") (pinfunction "EP_EP") (pintype "passive"))
      (node (ref "USS") (pin "4") (pinfunction "VSS_4") (pintype "power_in"))
      (node (ref "USS") (pin "EP") (pinfunction "EP_EP") (pintype "passive"))
      (node (ref "USW") (pin "4") (pinfunction "VSS_4") (pintype "power_in"))
      (node (ref "USW") (pin "EP") (pinfunction "EP_EP") (pintype "passive"))
      (node (ref "X-NORTH") (pin "102") (pinfunction "102_102") (pintype "bidirectional"))
      (node (ref "X-NORTH") (pin "103") (pinfunction "103_103") (pintype "bidirectional"))
      (node (ref "X-NORTH") (pin "108") (pinfunction "108_108") (pintype "bidirectional"))
      (node (ref "X-NORTH") (pin "114") (pinfunction "114_114") (pintype "bidirectional"))
      (node (ref "X-NORTH") (pin "12") (pinfunction "12_12") (pintype "bidirectional"))
      (node (ref "X-NORTH") (pin "120") (pinfunction "120_120") (pintype "bidirectional"))
      (node (ref "X-NORTH") (pin "126") (pinfunction "126_126") (pintype "bidirectional"))
      (node (ref "X-NORTH") (pin "132") (pinfunction "132_132") (pintype "bidirectional"))
      (node (ref "X-NORTH") (pin "138") (pinfunction "138_138") (pintype "bidirectional"))
      (node (ref "X-NORTH") (pin "139") (pinfunction "139_139") (pintype "bidirectional"))
      (node (ref "X-NORTH") (pin "18") (pinfunction "18_18") (pintype "bidirectional"))
      (node (ref "X-NORTH") (pin "24") (pinfunction "24_24") (pintype "bidirectional"))
      (node (ref "X-NORTH") (pin "30") (pinfunction "30_30") (pintype "bidirectional"))
      (node (ref "X-NORTH") (pin "36") (pinfunction "36_36") (pintype "bidirectional"))
      (node (ref "X-NORTH") (pin "42") (pinfunction "42_42") (pintype "bidirectional"))
      (node (ref "X-NORTH") (pin "43") (pinfunction "43_43") (pintype "bidirectional"))
      (node (ref "X-NORTH") (pin "48") (pinfunction "48_48") (pintype "bidirectional"))
      (node (ref "X-NORTH") (pin "54") (pinfunction "54_54") (pintype "bidirectional"))
      (node (ref "X-NORTH") (pin "60") (pinfunction "60_60") (pintype "bidirectional"))
      (node (ref "X-NORTH") (pin "66") (pinfunction "66_66") (pintype "bidirectional"))
      (node (ref "X-NORTH") (pin "72") (pinfunction "72_72") (pintype "bidirectional"))
      (node (ref "X-NORTH") (pin "78") (pinfunction "78_78") (pintype "bidirectional"))
      (node (ref "X-NORTH") (pin "84") (pinfunction "84_84") (pintype "bidirectional"))
      (node (ref "X-NORTH") (pin "90") (pinfunction "90_90") (pintype "bidirectional"))
      (node (ref "X-NORTH") (pin "96") (pinfunction "96_96") (pintype "bidirectional"))
      (node (ref "X-SOUTH") (pin "102") (pinfunction "102_102") (pintype "bidirectional"))
      (node (ref "X-SOUTH") (pin "103") (pinfunction "103_103") (pintype "bidirectional"))
      (node (ref "X-SOUTH") (pin "108") (pinfunction "108_108") (pintype "bidirectional"))
      (node (ref "X-SOUTH") (pin "114") (pinfunction "114_114") (pintype "bidirectional"))
      (node (ref "X-SOUTH") (pin "12") (pinfunction "12_12") (pintype "bidirectional"))
      (node (ref "X-SOUTH") (pin "120") (pinfunction "120_120") (pintype "bidirectional"))
      (node (ref "X-SOUTH") (pin "126") (pinfunction "126_126") (pintype "bidirectional"))
      (node (ref "X-SOUTH") (pin "132") (pinfunction "132_132") (pintype "bidirectional"))
      (node (ref "X-SOUTH") (pin "138") (pinfunction "138_138") (pintype "bidirectional"))
      (node (ref "X-SOUTH") (pin "139") (pinfunction "139_139") (pintype "bidirectional"))
      (node (ref "X-SOUTH") (pin "18") (pinfunction "18_18") (pintype "bidirectional"))
      (node (ref "X-SOUTH") (pin "24") (pinfunction "24_24") (pintype "bidirectional"))
      (node (ref "X-SOUTH") (pin "30") (pinfunction "30_30") (pintype "bidirectional"))
      (node (ref "X-SOUTH") (pin "36") (pinfunction "36_36") (pintype "bidirectional"))
      (node (ref "X-SOUTH") (pin "42") (pinfunction "42_42") (pintype "bidirectional"))
      (node (ref "X-SOUTH") (pin "43") (pinfunction "43_43") (pintype "bidirectional"))
      (node (ref "X-SOUTH") (pin "48") (pinfunction "48_48") (pintype "bidirectional"))
      (node (ref "X-SOUTH") (pin "54") (pinfunction "54_54") (pintype "bidirectional"))
      (node (ref "X-SOUTH") (pin "60") (pinfunction "60_60") (pintype "bidirectional"))
      (node (ref "X-SOUTH") (pin "66") (pinfunction "66_66") (pintype "bidirectional"))
      (node (ref "X-SOUTH") (pin "72") (pinfunction "72_72") (pintype "bidirectional"))
      (node (ref "X-SOUTH") (pin "78") (pinfunction "78_78") (pintype "bidirectional"))
      (node (ref "X-SOUTH") (pin "84") (pinfunction "84_84") (pintype "bidirectional"))
      (node (ref "X-SOUTH") (pin "90") (pinfunction "90_90") (pintype "bidirectional"))
      (node (ref "X-SOUTH") (pin "96") (pinfunction "96_96") (pintype "bidirectional"))
    )
    (net (code "4") (name "N$38") (class "Default")
      (node (ref "SENSOR") (pin "F4") (pinfunction "DIO1_F4") (pintype "output"))
    )
    (net (code "5") (name "N$39") (class "Default")
      (node (ref "SENSOR") (pin "E4") (pinfunction "DIO2_E4") (pintype "output"))
    )
    (net (code "6") (name "N$40") (class "Default")
      (node (ref "SENSOR") (pin "H4") (pinfunction "DIO3_H4") (pintype "output"))
    )
    (net (code "7") (name "N$41") (class "Default")
      (node (ref "SENSOR") (pin "G3") (pinfunction "DIO4_G3") (pintype "output"))
    )
    (net (code "8") (name "N$42") (class "Default")
      (node (ref "SENSOR") (pin "A2") (pinfunction "TANA_A2") (pintype "output"))
    )
    (net (code "9") (name "N00_N") (class "Default")
      (node (ref "R25") (pin "2") (pinfunction "2_2") (pintype "passive"))
      (node (ref "SENSOR") (pin "E6") (pinfunction "LVDS_CLK_P_E6") (pintype "input"))
      (node (ref "X-NORTH") (pin "16") (pinfunction "16_16") (pintype "bidirectional"))
    )
    (net (code "10") (name "N00_P") (class "Default")
      (node (ref "R25") (pin "1") (pinfunction "1_1") (pintype "passive"))
      (node (ref "SENSOR") (pin "E5") (pinfunction "LVDS_CLK_N_E5") (pintype "input"))
      (node (ref "X-NORTH") (pin "14") (pinfunction "14_14") (pintype "bidirectional"))
    )
    (net (code "11") (name "N01_N") (class "Default")
      (node (ref "SENSOR") (pin "G7") (pinfunction "OUTCLK_P_G7") (pintype "output"))
      (node (ref "X-NORTH") (pin "17") (pinfunction "17_17") (pintype "bidirectional"))
    )
    (net (code "12") (name "N01_P") (class "Default")
      (node (ref "SENSOR") (pin "G6") (pinfunction "OUTCLK_N_G6") (pintype "output"))
      (node (ref "X-NORTH") (pin "15") (pinfunction "15_15") (pintype "bidirectional"))
    )
    (net (code "13") (name "N02_N") (class "Default")
      (node (ref "SENSOR") (pin "F7") (pinfunction "OUT33_P_F7") (pintype "output"))
      (node (ref "X-NORTH") (pin "22") (pinfunction "22_22") (pintype "bidirectional"))
    )
    (net (code "14") (name "N02_P") (class "Default")
      (node (ref "SENSOR") (pin "F6") (pinfunction "OUT33_N_F6") (pintype "output"))
      (node (ref "X-NORTH") (pin "20") (pinfunction "20_20") (pintype "bidirectional"))
    )
    (net (code "15") (name "N03_N") (class "Default")
      (node (ref "X-NORTH") (pin "23") (pinfunction "23_23") (pintype "bidirectional"))
    )
    (net (code "16") (name "N03_P") (class "Default")
      (node (ref "X-NORTH") (pin "21") (pinfunction "21_21") (pintype "bidirectional"))
    )
    (net (code "17") (name "N04_N") (class "Default")
      (node (ref "SENSOR") (pin "E8") (pinfunction "OUT35_P_E8") (pintype "output"))
      (node (ref "X-NORTH") (pin "28") (pinfunction "28_28") (pintype "bidirectional"))
    )
    (net (code "18") (name "N04_P") (class "Default")
      (node (ref "SENSOR") (pin "E7") (pinfunction "OUT35_N_E7") (pintype "output"))
      (node (ref "X-NORTH") (pin "26") (pinfunction "26_26") (pintype "bidirectional"))
    )
    (net (code "19") (name "N05_N") (class "Default")
      (node (ref "SENSOR") (pin "H8") (pinfunction "OUT34_P_H8") (pintype "output"))
      (node (ref "X-NORTH") (pin "29") (pinfunction "29_29") (pintype "bidirectional"))
    )
    (net (code "20") (name "N05_P") (class "Default")
      (node (ref "SENSOR") (pin "H7") (pinfunction "OUT34_N_H7") (pintype "output"))
      (node (ref "X-NORTH") (pin "27") (pinfunction "27_27") (pintype "bidirectional"))
    )
    (net (code "21") (name "N06_N") (class "Default")
      (node (ref "SENSOR") (pin "F9") (pinfunction "OUT37_P_F9") (pintype "output"))
      (node (ref "X-NORTH") (pin "34") (pinfunction "34_34") (pintype "bidirectional"))
    )
    (net (code "22") (name "N06_P") (class "Default")
      (node (ref "SENSOR") (pin "F8") (pinfunction "OUT37_N_F8") (pintype "output"))
      (node (ref "X-NORTH") (pin "32") (pinfunction "32_32") (pintype "bidirectional"))
    )
    (net (code "23") (name "N07_N") (class "Default")
      (node (ref "SENSOR") (pin "G9") (pinfunction "OUT36_P_G9") (pintype "output"))
      (node (ref "X-NORTH") (pin "35") (pinfunction "35_35") (pintype "bidirectional"))
    )
    (net (code "24") (name "N07_P") (class "Default")
      (node (ref "SENSOR") (pin "G8") (pinfunction "OUT36_N_G8") (pintype "output"))
      (node (ref "X-NORTH") (pin "33") (pinfunction "33_33") (pintype "bidirectional"))
    )
    (net (code "25") (name "N08_N") (class "Default")
      (node (ref "SENSOR") (pin "E10") (pinfunction "OUT38_P_E10") (pintype "output"))
      (node (ref "X-NORTH") (pin "40") (pinfunction "40_40") (pintype "bidirectional"))
    )
    (net (code "26") (name "N08_P") (class "Default")
      (node (ref "SENSOR") (pin "E9") (pinfunction "OUT38_N_E9") (pintype "output"))
      (node (ref "X-NORTH") (pin "38") (pinfunction "38_38") (pintype "bidirectional"))
    )
    (net (code "27") (name "N09_N") (class "Default")
      (node (ref "SENSOR") (pin "G11") (pinfunction "OUT39_P_G11") (pintype "output"))
      (node (ref "X-NORTH") (pin "41") (pinfunction "41_41") (pintype "bidirectional"))
    )
    (net (code "28") (name "N09_P") (class "Default")
      (node (ref "SENSOR") (pin "G10") (pinfunction "OUT39_N_G10") (pintype "output"))
      (node (ref "X-NORTH") (pin "39") (pinfunction "39_39") (pintype "bidirectional"))
    )
    (net (code "29") (name "N10_N") (class "Default")
      (node (ref "SENSOR") (pin "F11") (pinfunction "OUT40_P_F11") (pintype "output"))
      (node (ref "X-NORTH") (pin "46") (pinfunction "46_46") (pintype "bidirectional"))
    )
    (net (code "30") (name "N10_P") (class "Default")
      (node (ref "SENSOR") (pin "F10") (pinfunction "OUT40_N_F10") (pintype "output"))
      (node (ref "X-NORTH") (pin "44") (pinfunction "44_44") (pintype "bidirectional"))
    )
    (net (code "31") (name "N11_N") (class "Default")
      (node (ref "SENSOR") (pin "H12") (pinfunction "OUT41_P_H12") (pintype "output"))
      (node (ref "X-NORTH") (pin "47") (pinfunction "47_47") (pintype "bidirectional"))
    )
    (net (code "32") (name "N11_P") (class "Default")
      (node (ref "SENSOR") (pin "H11") (pinfunction "OUT41_N_H11") (pintype "output"))
      (node (ref "X-NORTH") (pin "45") (pinfunction "45_45") (pintype "bidirectional"))
    )
    (net (code "33") (name "N12_N") (class "Default")
      (node (ref "SENSOR") (pin "E12") (pinfunction "OUT42_P_E12") (pintype "output"))
      (node (ref "X-NORTH") (pin "52") (pinfunction "52_52") (pintype "bidirectional"))
    )
    (net (code "34") (name "N12_P") (class "Default")
      (node (ref "SENSOR") (pin "E11") (pinfunction "OUT42_N_E11") (pintype "output"))
      (node (ref "X-NORTH") (pin "50") (pinfunction "50_50") (pintype "bidirectional"))
    )
    (net (code "35") (name "N13_N") (class "Default")
      (node (ref "SENSOR") (pin "G13") (pinfunction "OUT43_P_G13") (pintype "output"))
      (node (ref "X-NORTH") (pin "53") (pinfunction "53_53") (pintype "bidirectional"))
    )
    (net (code "36") (name "N13_P") (class "Default")
      (node (ref "SENSOR") (pin "G12") (pinfunction "OUT43_N_G12") (pintype "output"))
      (node (ref "X-NORTH") (pin "51") (pinfunction "51_51") (pintype "bidirectional"))
    )
    (net (code "37") (name "N14_N") (class "Default")
      (node (ref "SENSOR") (pin "F13") (pinfunction "OUT44_P_F13") (pintype "output"))
      (node (ref "X-NORTH") (pin "58") (pinfunction "58_58") (pintype "bidirectional"))
    )
    (net (code "38") (name "N14_P") (class "Default")
      (node (ref "SENSOR") (pin "F12") (pinfunction "OUT44_N_F12") (pintype "output"))
      (node (ref "X-NORTH") (pin "56") (pinfunction "56_56") (pintype "bidirectional"))
    )
    (net (code "39") (name "N15_N") (class "Default")
      (node (ref "SENSOR") (pin "H14") (pinfunction "OUT45_P_H14") (pintype "output"))
      (node (ref "X-NORTH") (pin "59") (pinfunction "59_59") (pintype "bidirectional"))
    )
    (net (code "40") (name "N15_P") (class "Default")
      (node (ref "SENSOR") (pin "H13") (pinfunction "OUT45_N_H13") (pintype "output"))
      (node (ref "X-NORTH") (pin "57") (pinfunction "57_57") (pintype "bidirectional"))
    )
    (net (code "41") (name "N16_N") (class "Default")
      (node (ref "SENSOR") (pin "E14") (pinfunction "OUT46_P_E14") (pintype "output"))
      (node (ref "X-NORTH") (pin "64") (pinfunction "64_64") (pintype "bidirectional"))
    )
    (net (code "42") (name "N16_P") (class "Default")
      (node (ref "SENSOR") (pin "E13") (pinfunction "OUT46_N_E13") (pintype "output"))
      (node (ref "X-NORTH") (pin "62") (pinfunction "62_62") (pintype "bidirectional"))
    )
    (net (code "43") (name "N17_N") (class "Default")
      (node (ref "SENSOR") (pin "G15") (pinfunction "OUT47_P_G15") (pintype "output"))
      (node (ref "X-NORTH") (pin "65") (pinfunction "65_65") (pintype "bidirectional"))
    )
    (net (code "44") (name "N17_P") (class "Default")
      (node (ref "SENSOR") (pin "G14") (pinfunction "OUT47_N_G14") (pintype "output"))
      (node (ref "X-NORTH") (pin "63") (pinfunction "63_63") (pintype "bidirectional"))
    )
    (net (code "45") (name "N18_N") (class "Default")
      (node (ref "SENSOR") (pin "F15") (pinfunction "OUT48_P_F15") (pintype "output"))
      (node (ref "X-NORTH") (pin "70") (pinfunction "70_70") (pintype "bidirectional"))
    )
    (net (code "46") (name "N18_P") (class "Default")
      (node (ref "SENSOR") (pin "F14") (pinfunction "OUT48_N_F14") (pintype "output"))
      (node (ref "X-NORTH") (pin "68") (pinfunction "68_68") (pintype "bidirectional"))
    )
    (net (code "47") (name "N19_N") (class "Default")
      (node (ref "SENSOR") (pin "G17") (pinfunction "OUT50_P_G17") (pintype "output"))
      (node (ref "X-NORTH") (pin "71") (pinfunction "71_71") (pintype "bidirectional"))
    )
    (net (code "48") (name "N19_P") (class "Default")
      (node (ref "SENSOR") (pin "G16") (pinfunction "OUT50_N_G16") (pintype "output"))
      (node (ref "X-NORTH") (pin "69") (pinfunction "69_69") (pintype "bidirectional"))
    )
    (net (code "49") (name "N20_N") (class "Default")
      (node (ref "SENSOR") (pin "F17") (pinfunction "OUT49_P_F17") (pintype "output"))
      (node (ref "X-NORTH") (pin "76") (pinfunction "76_76") (pintype "bidirectional"))
    )
    (net (code "50") (name "N20_P") (class "Default")
      (node (ref "SENSOR") (pin "F16") (pinfunction "OUT49_N_F16") (pintype "output"))
      (node (ref "X-NORTH") (pin "74") (pinfunction "74_74") (pintype "bidirectional"))
    )
    (net (code "51") (name "N21_N") (class "Default")
      (node (ref "SENSOR") (pin "H18") (pinfunction "OUT52_P_H18") (pintype "output"))
      (node (ref "X-NORTH") (pin "77") (pinfunction "77_77") (pintype "bidirectional"))
    )
    (net (code "52") (name "N21_P") (class "Default")
      (node (ref "SENSOR") (pin "H17") (pinfunction "OUT52_N_H17") (pintype "output"))
      (node (ref "X-NORTH") (pin "75") (pinfunction "75_75") (pintype "bidirectional"))
    )
    (net (code "53") (name "N22_N") (class "Default")
      (node (ref "SENSOR") (pin "E18") (pinfunction "OUT51_P_E18") (pintype "output"))
      (node (ref "X-NORTH") (pin "82") (pinfunction "82_82") (pintype "bidirectional"))
    )
    (net (code "54") (name "N22_P") (class "Default")
      (node (ref "SENSOR") (pin "E17") (pinfunction "OUT51_N_E17") (pintype "output"))
      (node (ref "X-NORTH") (pin "80") (pinfunction "80_80") (pintype "bidirectional"))
    )
    (net (code "55") (name "N23_N") (class "Default")
      (node (ref "SENSOR") (pin "G19") (pinfunction "OUT54_P_G19") (pintype "output"))
      (node (ref "X-NORTH") (pin "83") (pinfunction "83_83") (pintype "bidirectional"))
    )
    (net (code "56") (name "N23_P") (class "Default")
      (node (ref "SENSOR") (pin "G18") (pinfunction "OUT54_N_G18") (pintype "output"))
      (node (ref "X-NORTH") (pin "81") (pinfunction "81_81") (pintype "bidirectional"))
    )
    (net (code "57") (name "N24_N") (class "Default")
      (node (ref "SENSOR") (pin "F19") (pinfunction "OUT53_P_F19") (pintype "output"))
      (node (ref "X-NORTH") (pin "88") (pinfunction "88_88") (pintype "bidirectional"))
    )
    (net (code "58") (name "N24_P") (class "Default")
      (node (ref "SENSOR") (pin "F18") (pinfunction "OUT53_N_F18") (pintype "output"))
      (node (ref "X-NORTH") (pin "86") (pinfunction "86_86") (pintype "bidirectional"))
    )
    (net (code "59") (name "N25_N") (class "Default")
      (node (ref "SENSOR") (pin "H20") (pinfunction "OUT56_P_H20") (pintype "output"))
      (node (ref "X-NORTH") (pin "89") (pinfunction "89_89") (pintype "bidirectional"))
    )
    (net (code "60") (name "N25_P") (class "Default")
      (node (ref "SENSOR") (pin "H19") (pinfunction "OUT56_N_H19") (pintype "output"))
      (node (ref "X-NORTH") (pin "87") (pinfunction "87_87") (pintype "bidirectional"))
    )
    (net (code "61") (name "N26_N") (class "Default")
      (node (ref "SENSOR") (pin "E20") (pinfunction "OUT55_P_E20") (pintype "output"))
      (node (ref "X-NORTH") (pin "94") (pinfunction "94_94") (pintype "bidirectional"))
    )
    (net (code "62") (name "N26_P") (class "Default")
      (node (ref "SENSOR") (pin "E19") (pinfunction "OUT55_N_E19") (pintype "output"))
      (node (ref "X-NORTH") (pin "92") (pinfunction "92_92") (pintype "bidirectional"))
    )
    (net (code "63") (name "N27_N") (class "Default")
      (node (ref "SENSOR") (pin "G21") (pinfunction "OUT58_P_G21") (pintype "output"))
      (node (ref "X-NORTH") (pin "95") (pinfunction "95_95") (pintype "bidirectional"))
    )
    (net (code "64") (name "N27_P") (class "Default")
      (node (ref "SENSOR") (pin "G20") (pinfunction "OUT58_N_G20") (pintype "output"))
      (node (ref "X-NORTH") (pin "93") (pinfunction "93_93") (pintype "bidirectional"))
    )
    (net (code "65") (name "N28_N") (class "Default")
      (node (ref "SENSOR") (pin "F21") (pinfunction "OUT57_P_F21") (pintype "output"))
      (node (ref "X-NORTH") (pin "100") (pinfunction "100_100") (pintype "bidirectional"))
    )
    (net (code "66") (name "N28_P") (class "Default")
      (node (ref "SENSOR") (pin "F20") (pinfunction "OUT57_N_F20") (pintype "output"))
      (node (ref "X-NORTH") (pin "98") (pinfunction "98_98") (pintype "bidirectional"))
    )
    (net (code "67") (name "N29_N") (class "Default")
      (node (ref "SENSOR") (pin "G23") (pinfunction "OUT61_P_G23") (pintype "output"))
      (node (ref "X-NORTH") (pin "101") (pinfunction "101_101") (pintype "bidirectional"))
    )
    (net (code "68") (name "N29_P") (class "Default")
      (node (ref "SENSOR") (pin "G22") (pinfunction "OUT61_N_G22") (pintype "output"))
      (node (ref "X-NORTH") (pin "99") (pinfunction "99_99") (pintype "bidirectional"))
    )
    (net (code "69") (name "N30_N") (class "Default")
      (node (ref "SENSOR") (pin "E22") (pinfunction "OUT59_P_E22") (pintype "output"))
      (node (ref "X-NORTH") (pin "106") (pinfunction "106_106") (pintype "bidirectional"))
    )
    (net (code "70") (name "N30_P") (class "Default")
      (node (ref "SENSOR") (pin "E21") (pinfunction "OUT59_N_E21") (pintype "output"))
      (node (ref "X-NORTH") (pin "104") (pinfunction "104_104") (pintype "bidirectional"))
    )
    (net (code "71") (name "N31_N") (class "Default")
      (node (ref "SENSOR") (pin "H24") (pinfunction "OUT63_P_H24") (pintype "output"))
      (node (ref "X-NORTH") (pin "107") (pinfunction "107_107") (pintype "bidirectional"))
    )
    (net (code "72") (name "N31_P") (class "Default")
      (node (ref "SENSOR") (pin "H23") (pinfunction "OUT63_N_H23") (pintype "output"))
      (node (ref "X-NORTH") (pin "105") (pinfunction "105_105") (pintype "bidirectional"))
    )
    (net (code "73") (name "N32_N") (class "Default")
      (node (ref "SENSOR") (pin "F23") (pinfunction "OUT60_P_F23") (pintype "output"))
      (node (ref "X-NORTH") (pin "112") (pinfunction "112_112") (pintype "bidirectional"))
    )
    (net (code "74") (name "N32_P") (class "Default")
      (node (ref "SENSOR") (pin "F22") (pinfunction "OUT60_N_F22") (pintype "output"))
      (node (ref "X-NORTH") (pin "110") (pinfunction "110_110") (pintype "bidirectional"))
    )
    (net (code "75") (name "N33_N") (class "Default")
      (node (ref "SENSOR") (pin "G25") (pinfunction "OUT64_P_G25") (pintype "output"))
      (node (ref "X-NORTH") (pin "113") (pinfunction "113_113") (pintype "bidirectional"))
    )
    (net (code "76") (name "N33_P") (class "Default")
      (node (ref "SENSOR") (pin "G24") (pinfunction "OUT64_N_G24") (pintype "output"))
      (node (ref "X-NORTH") (pin "111") (pinfunction "111_111") (pintype "bidirectional"))
    )
    (net (code "77") (name "N34_N") (class "Default")
      (node (ref "SENSOR") (pin "E24") (pinfunction "OUT62_P_E24") (pintype "output"))
      (node (ref "X-NORTH") (pin "118") (pinfunction "118_118") (pintype "bidirectional"))
    )
    (net (code "78") (name "N34_P") (class "Default")
      (node (ref "SENSOR") (pin "E23") (pinfunction "OUT62_N_E23") (pintype "output"))
      (node (ref "X-NORTH") (pin "116") (pinfunction "116_116") (pintype "bidirectional"))
    )
    (net (code "79") (name "N35_N") (class "Default")
      (node (ref "U6") (pin "4") (pinfunction "A4_4") (pintype "bidirectional"))
      (node (ref "X-NORTH") (pin "119") (pinfunction "119_119") (pintype "bidirectional"))
    )
    (net (code "80") (name "N35_P") (class "Default")
      (node (ref "U6") (pin "3") (pinfunction "A3_3") (pintype "bidirectional"))
      (node (ref "X-NORTH") (pin "117") (pinfunction "117_117") (pintype "bidirectional"))
    )
    (net (code "81") (name "N36_N") (class "Default")
      (node (ref "X-NORTH") (pin "124") (pinfunction "124_124") (pintype "bidirectional"))
    )
    (net (code "82") (name "N36_P") (class "Default")
      (node (ref "X-NORTH") (pin "122") (pinfunction "122_122") (pintype "bidirectional"))
    )
    (net (code "83") (name "N37_N") (class "Default")
      (node (ref "U5") (pin "3") (pinfunction "A3_3") (pintype "bidirectional"))
      (node (ref "X-NORTH") (pin "125") (pinfunction "125_125") (pintype "bidirectional"))
    )
    (net (code "84") (name "N37_P") (class "Default")
      (node (ref "U5") (pin "4") (pinfunction "A4_4") (pintype "bidirectional"))
      (node (ref "X-NORTH") (pin "123") (pinfunction "123_123") (pintype "bidirectional"))
    )
    (net (code "85") (name "N38_N") (class "Default")
      (node (ref "U6") (pin "2") (pinfunction "A2_2") (pintype "bidirectional"))
      (node (ref "X-NORTH") (pin "130") (pinfunction "130_130") (pintype "bidirectional"))
    )
    (net (code "86") (name "N38_P") (class "Default")
      (node (ref "U6") (pin "1") (pinfunction "A1_1") (pintype "bidirectional"))
      (node (ref "X-NORTH") (pin "128") (pinfunction "128_128") (pintype "bidirectional"))
    )
    (net (code "87") (name "N39_N") (class "Default")
      (node (ref "U5") (pin "1") (pinfunction "A1_1") (pintype "bidirectional"))
      (node (ref "X-NORTH") (pin "131") (pinfunction "131_131") (pintype "bidirectional"))
    )
    (net (code "88") (name "N39_P") (class "Default")
      (node (ref "U5") (pin "2") (pinfunction "A2_2") (pintype "bidirectional"))
      (node (ref "X-NORTH") (pin "129") (pinfunction "129_129") (pintype "bidirectional"))
    )
    (net (code "89") (name "N_CHK_V") (class "Default")
      (node (ref "C2") (pin "1") (pinfunction "1_1") (pintype "passive"))
      (node (ref "C3") (pin "1") (pinfunction "1_1") (pintype "passive"))
      (node (ref "C4") (pin "1") (pinfunction "1_1") (pintype "passive"))
      (node (ref "R19") (pin "1") (pinfunction "1_1") (pintype "passive"))
      (node (ref "TP1") (pin "TP") (pinfunction "TP_TP") (pintype "input"))
      (node (ref "UNE") (pin "8") (pinfunction "VDD_8") (pintype "power_in"))
      (node (ref "UNN") (pin "8") (pinfunction "VDD_8") (pintype "power_in"))
      (node (ref "UNW") (pin "8") (pinfunction "VDD_8") (pintype "power_in"))
      (node (ref "X-NORTH") (pin "10") (pinfunction "10_10") (pintype "bidirectional"))
      (node (ref "X-NORTH") (pin "8") (pinfunction "8_8") (pintype "bidirectional"))
    )
    (net (code "90") (name "N_I2C_V") (class "Default")
      (node (ref "C1") (pin "1") (pinfunction "1_1") (pintype "passive"))
      (node (ref "R1X") (pin "1") (pinfunction "1_1") (pintype "passive"))
      (node (ref "UEP") (pin "8") (pinfunction "VCC_8") (pintype "power_in"))
      (node (ref "X-NORTH") (pin "135") (pinfunction "135_135") (pintype "bidirectional"))
      (node (ref "X-NORTH") (pin "137") (pinfunction "137_137") (pintype "bidirectional"))
    )
    (net (code "91") (name "N_REF") (class "Default")
      (node (ref "R19") (pin "2") (pinfunction "2_2") (pintype "passive"))
      (node (ref "TP2") (pin "TP") (pinfunction "TP_TP") (pintype "input"))
      (node (ref "U1") (pin "1") (pinfunction "CATHODE_1") (pintype "output"))
      (node (ref "U1") (pin "3") (pinfunction "REF_3") (pintype "input"))
      (node (ref "UNE") (pin "2") (pinfunction "VINA-_2") (pintype "input"))
      (node (ref "UNE") (pin "5") (pinfunction "VINB+_5") (pintype "input"))
      (node (ref "UNN") (pin "2") (pinfunction "VINA-_2") (pintype "input"))
      (node (ref "UNN") (pin "5") (pinfunction "VINB+_5") (pintype "input"))
      (node (ref "UNW") (pin "2") (pinfunction "VINA-_2") (pintype "input"))
      (node (ref "UNW") (pin "5") (pinfunction "VINB+_5") (pintype "input"))
    )
    (net (code "92") (name "N_SCK") (class "Default")
      (node (ref "U4") (pin "15") (pinfunction "1B1_15") (pintype "output"))
      (node (ref "X-NORTH") (pin "144") (pinfunction "144_144") (pintype "bidirectional"))
    )
    (net (code "93") (name "N_SCL") (class "Default")
      (node (ref "UEP") (pin "6") (pinfunction "SCL_6") (pintype "input"))
      (node (ref "X-NORTH") (pin "143") (pinfunction "143_143") (pintype "bidirectional"))
    )
    (net (code "94") (name "N_SDA") (class "Default")
      (node (ref "UEP") (pin "5") (pinfunction "SDA_5") (pintype "bidirectional"))
      (node (ref "X-NORTH") (pin "141") (pinfunction "141_141") (pintype "bidirectional"))
    )
    (net (code "95") (name "N_SDI") (class "Default")
      (node (ref "U4") (pin "13") (pinfunction "2B1_13") (pintype "output"))
      (node (ref "X-NORTH") (pin "140") (pinfunction "140_140") (pintype "bidirectional"))
    )
    (net (code "96") (name "N_SDO") (class "Default")
      (node (ref "U4") (pin "14") (pinfunction "1B2_14") (pintype "output"))
      (node (ref "X-NORTH") (pin "142") (pinfunction "142_142") (pintype "bidirectional"))
    )
    (net (code "97") (name "N_SPI_V") (class "Default")
      (node (ref "C59") (pin "1") (pinfunction "1_1") (pintype "passive"))
      (node (ref "U4") (pin "2") (pinfunction "VCCB_2") (pintype "power_in"))
      (node (ref "X-NORTH") (pin "134") (pinfunction "134_134") (pintype "bidirectional"))
      (node (ref "X-NORTH") (pin "136") (pinfunction "136_136") (pintype "bidirectional"))
    )
    (net (code "98") (name "N_VE") (class "Default")
      (node (ref "C50") (pin "1") (pinfunction "1_1") (pintype "passive"))
      (node (ref "C51") (pin "1") (pinfunction "1_1") (pintype "passive"))
      (node (ref "C52") (pin "1") (pinfunction "1_1") (pintype "passive"))
      (node (ref "C53") (pin "1") (pinfunction "1_1") (pintype "passive"))
      (node (ref "C54") (pin "1") (pinfunction "1_1") (pintype "passive"))
      (node (ref "C55") (pin "1") (pinfunction "1_1") (pintype "passive"))
      (node (ref "C56") (pin "1") (pinfunction "1_1") (pintype "passive"))
      (node (ref "C67") (pin "1") (pinfunction "1_1") (pintype "passive"))
      (node (ref "C69") (pin "1") (pinfunction "1_1") (pintype "passive"))
      (node (ref "C75") (pin "1") (pinfunction "1_1") (pintype "passive"))
      (node (ref "C76") (pin "1") (pinfunction "1_1") (pintype "passive"))
      (node (ref "C77") (pin "1") (pinfunction "1_1") (pintype "passive"))
      (node (ref "C84") (pin "1") (pinfunction "1_1") (pintype "passive"))
      (node (ref "C85") (pin "1") (pinfunction "1_1") (pintype "passive"))
      (node (ref "C86") (pin "1") (pinfunction "1_1") (pintype "passive"))
      (node (ref "SENSOR") (pin "C26") (pinfunction "VDD33_C26") (pintype "power_in"))
      (node (ref "SENSOR") (pin "C27") (pinfunction "VDD33_C27") (pintype "power_in"))
      (node (ref "SENSOR") (pin "D26") (pinfunction "VDD33_D26") (pintype "power_in"))
      (node (ref "SENSOR") (pin "D3") (pinfunction "VDD33_D3") (pintype "power_in"))
      (node (ref "SENSOR") (pin "E26") (pinfunction "VDD33_E26") (pintype "power_in"))
      (node (ref "SENSOR") (pin "F26") (pinfunction "VDD33_F26") (pintype "power_in"))
      (node (ref "SENSOR") (pin "F5") (pinfunction "VDD33_F5") (pintype "power_in"))
      (node (ref "TP7") (pin "TP") (pinfunction "TP_TP") (pintype "input"))
      (node (ref "U4") (pin "3") (pinfunction "VCCA_3") (pintype "power_in"))
      (node (ref "U4") (pin "5") (pinfunction "2DIR_5") (pintype "input"))
      (node (ref "U5") (pin "13") (pinfunction "VCCB_13") (pintype "power_in"))
      (node (ref "U6") (pin "13") (pinfunction "VCCB_13") (pintype "power_in"))
      (node (ref "X-NORTH") (pin "109") (pinfunction "109_109") (pintype "bidirectional"))
      (node (ref "X-NORTH") (pin "115") (pinfunction "115_115") (pintype "bidirectional"))
      (node (ref "X-NORTH") (pin "121") (pinfunction "121_121") (pintype "bidirectional"))
      (node (ref "X-NORTH") (pin "127") (pinfunction "127_127") (pintype "bidirectional"))
      (node (ref "X-NORTH") (pin "133") (pinfunction "133_133") (pintype "bidirectional"))
    )
    (net (code "99") (name "N_VE_CV") (class "Default")
      (node (ref "C10") (pin "1") (pinfunction "1_1") (pintype "passive"))
      (node (ref "R7") (pin "1") (pinfunction "1_1") (pintype "passive"))
      (node (ref "X-NORTH") (pin "6") (pinfunction "6_6") (pintype "bidirectional"))
    )
    (net (code "100") (name "N_VE_OV") (class "Default")
      (node (ref "UNE") (pin "7") (pinfunction "OUTB_7") (pintype "output"))
      (node (ref "X-NORTH") (pin "5") (pinfunction "5_5") (pintype "bidirectional"))
    )
    (net (code "101") (name "N_VE_UV") (class "Default")
      (node (ref "UNE") (pin "1") (pinfunction "OUTA_1") (pintype "output"))
      (node (ref "X-NORTH") (pin "11") (pinfunction "11_11") (pintype "bidirectional"))
    )
    (net (code "102") (name "N_VN") (class "Default")
      (node (ref "C31") (pin "1") (pinfunction "1_1") (pintype "passive"))
      (node (ref "C32") (pin "1") (pinfunction "1_1") (pintype "passive"))
      (node (ref "C33") (pin "1") (pinfunction "1_1") (pintype "passive"))
      (node (ref "C34") (pin "1") (pinfunction "1_1") (pintype "passive"))
      (node (ref "C35") (pin "1") (pinfunction "1_1") (pintype "passive"))
      (node (ref "C36") (pin "1") (pinfunction "1_1") (pintype "passive"))
      (node (ref "C37") (pin "1") (pinfunction "1_1") (pintype "passive"))
      (node (ref "C38") (pin "1") (pinfunction "1_1") (pintype "passive"))
      (node (ref "C39") (pin "1") (pinfunction "1_1") (pintype "passive"))
      (node (ref "C40") (pin "1") (pinfunction "1_1") (pintype "passive"))
      (node (ref "C41") (pin "1") (pinfunction "1_1") (pintype "passive"))
      (node (ref "C42") (pin "1") (pinfunction "1_1") (pintype "passive"))
      (node (ref "C43") (pin "1") (pinfunction "1_1") (pintype "passive"))
      (node (ref "C44") (pin "1") (pinfunction "1_1") (pintype "passive"))
      (node (ref "C68") (pin "1") (pinfunction "1_1") (pintype "passive"))
      (node (ref "C70") (pin "1") (pinfunction "1_1") (pintype "passive"))
      (node (ref "C78") (pin "1") (pinfunction "1_1") (pintype "passive"))
      (node (ref "C79") (pin "1") (pinfunction "1_1") (pintype "passive"))
      (node (ref "C80") (pin "1") (pinfunction "1_1") (pintype "passive"))
      (node (ref "C87") (pin "1") (pinfunction "1_1") (pintype "passive"))
      (node (ref "C88") (pin "1") (pinfunction "1_1") (pintype "passive"))
      (node (ref "C89") (pin "1") (pinfunction "1_1") (pintype "passive"))
      (node (ref "SENSOR") (pin "A10") (pinfunction "VDD18_A10") (pintype "power_in"))
      (node (ref "SENSOR") (pin "A15") (pinfunction "VDD18_A15") (pintype "power_in"))
      (node (ref "SENSOR") (pin "A16") (pinfunction "VDD18_A16") (pintype "power_in"))
      (node (ref "SENSOR") (pin "A22") (pinfunction "VDD18_A22") (pintype "power_in"))
      (node (ref "SENSOR") (pin "A26") (pinfunction "VDD18_A26") (pintype "power_in"))
      (node (ref "SENSOR") (pin "A27") (pinfunction "VDD18_A27") (pintype "power_in"))
      (node (ref "SENSOR") (pin "B4") (pinfunction "VDD18_B4") (pintype "power_in"))
      (node (ref "SENSOR") (pin "E1") (pinfunction "VDD18_PLL_E1") (pintype "power_in"))
      (node (ref "SENSOR") (pin "H10") (pinfunction "VDD18_H10") (pintype "power_in"))
      (node (ref "SENSOR") (pin "H15") (pinfunction "VDD18_H15") (pintype "power_in"))
      (node (ref "SENSOR") (pin "H16") (pinfunction "VDD18_H16") (pintype "power_in"))
      (node (ref "SENSOR") (pin "H22") (pinfunction "VDD18_H22") (pintype "power_in"))
      (node (ref "SENSOR") (pin "H26") (pinfunction "VDD18_H26") (pintype "power_in"))
      (node (ref "SENSOR") (pin "H5") (pinfunction "VDD18_H5") (pintype "power_in"))
      (node (ref "TP5") (pin "TP") (pinfunction "TP_TP") (pintype "input"))
      (node (ref "U5") (pin "14") (pinfunction "VCCA_14") (pintype "power_in"))
      (node (ref "U5") (pin "15") (pinfunction "DIR1_15") (pintype "input"))
      (node (ref "U5") (pin "16") (pinfunction "DIR2_16") (pintype "input"))
      (node (ref "U5") (pin "5") (pinfunction "DIR3_5") (pintype "input"))
      (node (ref "U6") (pin "14") (pinfunction "VCCA_14") (pintype "power_in"))
      (node (ref "U6") (pin "15") (pinfunction "DIR1_15") (pintype "input"))
      (node (ref "U6") (pin "5") (pinfunction "DIR3_5") (pintype "input"))
      (node (ref "U6") (pin "6") (pinfunction "DIR4_6") (pintype "input"))
      (node (ref "X-NORTH") (pin "49") (pinfunction "49_49") (pintype "bidirectional"))
      (node (ref "X-NORTH") (pin "55") (pinfunction "55_55") (pintype "bidirectional"))
      (node (ref "X-NORTH") (pin "61") (pinfunction "61_61") (pintype "bidirectional"))
      (node (ref "X-NORTH") (pin "67") (pinfunction "67_67") (pintype "bidirectional"))
      (node (ref "X-NORTH") (pin "73") (pinfunction "73_73") (pintype "bidirectional"))
      (node (ref "X-NORTH") (pin "79") (pinfunction "79_79") (pintype "bidirectional"))
      (node (ref "X-NORTH") (pin "85") (pinfunction "85_85") (pintype "bidirectional"))
      (node (ref "X-NORTH") (pin "91") (pinfunction "91_91") (pintype "bidirectional"))
      (node (ref "X-NORTH") (pin "97") (pinfunction "97_97") (pintype "bidirectional"))
    )
    (net (code "103") (name "N_VN_CV") (class "Default")
      (node (ref "C9") (pin "1") (pinfunction "1_1") (pintype "passive"))
      (node (ref "R4") (pin "1") (pinfunction "1_1") (pintype "passive"))
      (node (ref "X-NORTH") (pin "4") (pinfunction "4_4") (pintype "bidirectional"))
    )
    (net (code "104") (name "N_VN_OV") (class "Default")
      (node (ref "UNN") (pin "7") (pinfunction "OUTB_7") (pintype "output"))
      (node (ref "X-NORTH") (pin "3") (pinfunction "3_3") (pintype "bidirectional"))
    )
    (net (code "105") (name "N_VN_UV") (class "Default")
      (node (ref "UNN") (pin "1") (pinfunction "OUTA_1") (pintype "output"))
      (node (ref "X-NORTH") (pin "9") (pinfunction "9_9") (pintype "bidirectional"))
    )
    (net (code "106") (name "N_VW") (class "Default")
      (node (ref "C57") (pin "1") (pinfunction "1_1") (pintype "passive"))
      (node (ref "C58") (pin "1") (pinfunction "1_1") (pintype "passive"))
      (node (ref "C92") (pin "1") (pinfunction "1_1") (pintype "passive"))
      (node (ref "SENSOR") (pin "E2") (pinfunction "VDD_RES_E2") (pintype "power_in"))
      (node (ref "SENSOR") (pin "G4") (pinfunction "VDD_RES_G4") (pintype "power_in"))
      (node (ref "TP8") (pin "TP") (pinfunction "TP_TP") (pintype "input"))
      (node (ref "X-NORTH") (pin "13") (pinfunction "13_13") (pintype "bidirectional"))
      (node (ref "X-NORTH") (pin "19") (pinfunction "19_19") (pintype "bidirectional"))
      (node (ref "X-NORTH") (pin "25") (pinfunction "25_25") (pintype "bidirectional"))
      (node (ref "X-NORTH") (pin "31") (pinfunction "31_31") (pintype "bidirectional"))
      (node (ref "X-NORTH") (pin "37") (pinfunction "37_37") (pintype "bidirectional"))
    )
    (net (code "107") (name "N_VW_CV") (class "Default")
      (node (ref "C8") (pin "1") (pinfunction "1_1") (pintype "passive"))
      (node (ref "R1") (pin "1") (pinfunction "1_1") (pintype "passive"))
      (node (ref "X-NORTH") (pin "2") (pinfunction "2_2") (pintype "bidirectional"))
    )
    (net (code "108") (name "N_VW_OV") (class "Default")
      (node (ref "UNW") (pin "7") (pinfunction "OUTB_7") (pintype "output"))
      (node (ref "X-NORTH") (pin "1") (pinfunction "1_1") (pintype "bidirectional"))
    )
    (net (code "109") (name "N_VW_UV") (class "Default")
      (node (ref "UNW") (pin "1") (pinfunction "OUTA_1") (pintype "output"))
      (node (ref "X-NORTH") (pin "7") (pinfunction "7_7") (pintype "bidirectional"))
    )
    (net (code "110") (name "Net-(SENSORB-CMDN)") (class "Default")
      (node (ref "C61") (pin "1") (pinfunction "1_1") (pintype "passive"))
      (node (ref "SENSOR") (pin "F1") (pinfunction "CMDN_F1") (pintype "bidirectional"))
    )
    (net (code "111") (name "Net-(SENSORB-CMDP)") (class "Default")
      (node (ref "C22") (pin "2") (pinfunction "2_2") (pintype "passive"))
      (node (ref "SENSOR") (pin "F2") (pinfunction "CMDP_F2") (pintype "bidirectional"))
    )
    (net (code "112") (name "Net-(SENSORB-CMDP_COMP)") (class "Default")
      (node (ref "C28") (pin "2") (pinfunction "2_2") (pintype "passive"))
      (node (ref "SENSOR") (pin "H3") (pinfunction "CMDP_COMP_H3") (pintype "bidirectional"))
    )
    (net (code "113") (name "Net-(SENSORB-CMDP_COMP_INV)") (class "Default")
      (node (ref "C27") (pin "2") (pinfunction "2_2") (pintype "passive"))
      (node (ref "SENSOR") (pin "F3") (pinfunction "CMDP_COMP_INV_F3") (pintype "bidirectional"))
    )
    (net (code "114") (name "Net-(SENSORB-CMD_COLAMP)") (class "Default")
      (node (ref "C25") (pin "2") (pinfunction "2_2") (pintype "passive"))
      (node (ref "SENSOR") (pin "C6") (pinfunction "CMD_COLAMP_C6") (pintype "bidirectional"))
    )
    (net (code "115") (name "Net-(SENSORB-CMD_COL_LOAD)") (class "Default")
      (node (ref "C23") (pin "2") (pinfunction "2_2") (pintype "passive"))
      (node (ref "SENSOR") (pin "B1") (pinfunction "CMD_COL_LOAD_B1") (pintype "bidirectional"))
    )
    (net (code "116") (name "Net-(SENSORB-CMD_COL_PC)") (class "Default")
      (node (ref "C26") (pin "2") (pinfunction "2_2") (pintype "passive"))
      (node (ref "SENSOR") (pin "D1") (pinfunction "CMD_COL_PC_D1") (pintype "bidirectional"))
    )
    (net (code "117") (name "Net-(SENSORB-CMD_LVDS)") (class "Default")
      (node (ref "C62") (pin "1") (pinfunction "1_1") (pintype "passive"))
      (node (ref "SENSOR") (pin "C1") (pinfunction "CMD_LVDS_C1") (pintype "bidirectional"))
    )
    (net (code "118") (name "Net-(SENSORB-CMD_RAMP)") (class "Default")
      (node (ref "C24") (pin "2") (pinfunction "2_2") (pintype "passive"))
      (node (ref "SENSOR") (pin "B29") (pinfunction "CMD_RAMP_B29") (pintype "bidirectional"))
    )
    (net (code "119") (name "Net-(SENSORB-VBGAP)") (class "Default")
      (node (ref "C64") (pin "1") (pinfunction "1_1") (pintype "passive"))
      (node (ref "SENSOR") (pin "C29") (pinfunction "VBGAP_C29") (pintype "bidirectional"))
    )
    (net (code "120") (name "Net-(SENSORB-VCLAMP)") (class "Default")
      (node (ref "C63") (pin "1") (pinfunction "1_1") (pintype "passive"))
      (node (ref "SENSOR") (pin "D4") (pinfunction "VCLAMP_D4") (pintype "bidirectional"))
    )
    (net (code "121") (name "Net-(SENSORB-VCLAMP_ADC)") (class "Default")
      (node (ref "C60") (pin "1") (pinfunction "1_1") (pintype "passive"))
      (node (ref "SENSOR") (pin "G2") (pinfunction "VCLAMP_ADC_G2") (pintype "bidirectional"))
    )
    (net (code "122") (name "Net-(SENSORB-VPCH_H)") (class "Default")
      (node (ref "C71") (pin "1") (pinfunction "1_1") (pintype "passive"))
      (node (ref "SENSOR") (pin "C4") (pinfunction "VPCH_H_C4") (pintype "bidirectional"))
    )
    (net (code "123") (name "Net-(SENSORB-VPCH_L)") (class "Default")
      (node (ref "C14") (pin "1") (pinfunction "1_1") (pintype "passive"))
      (node (ref "SENSOR") (pin "A4") (pinfunction "VPCH_L_A4") (pintype "bidirectional"))
    )
    (net (code "124") (name "Net-(SENSORB-VREF)") (class "Default")
      (node (ref "C29") (pin "1") (pinfunction "1_1") (pintype "passive"))
      (node (ref "SENSOR") (pin "A3") (pinfunction "VREF_A3") (pintype "bidirectional"))
    )
    (net (code "125") (name "Net-(SENSORB-VREF_ADC)") (class "Default")
      (node (ref "C30") (pin "1") (pinfunction "1_1") (pintype "passive"))
      (node (ref "SENSOR") (pin "B3") (pinfunction "VREF_ADC_B3") (pintype "bidirectional"))
    )
    (net (code "126") (name "Net-(SENSORB-VRES_L)") (class "Default")
      (node (ref "C15") (pin "1") (pinfunction "1_1") (pintype "passive"))
      (node (ref "SENSOR") (pin "D5") (pinfunction "VRES_L_D5") (pintype "bidirectional"))
    )
    (net (code "127") (name "Net-(SENSORB-VTF_LOW0)") (class "Default")
      (node (ref "C18") (pin "1") (pinfunction "1_1") (pintype "passive"))
      (node (ref "SENSOR") (pin "C5") (pinfunction "VTF_LOW0_C5") (pintype "bidirectional"))
    )
    (net (code "128") (name "Net-(SENSORB-VTF_LOW1)") (class "Default")
      (node (ref "C19") (pin "1") (pinfunction "1_1") (pintype "passive"))
      (node (ref "SENSOR") (pin "D6") (pinfunction "VTF_LOW1_D6") (pintype "bidirectional"))
    )
    (net (code "129") (name "Net-(SENSORB-VTF_LOW2)") (class "Default")
      (node (ref "C20") (pin "1") (pinfunction "1_1") (pintype "passive"))
      (node (ref "SENSOR") (pin "B30") (pinfunction "VTF_LOW2_B30") (pintype "bidirectional"))
    )
    (net (code "130") (name "Net-(SENSORB-VTF_LOW3)") (class "Default")
      (node (ref "C21") (pin "1") (pinfunction "1_1") (pintype "passive"))
      (node (ref "SENSOR") (pin "C30") (pinfunction "VTF_LOW3_C30") (pintype "bidirectional"))
    )
    (net (code "131") (name "Net-(U3-ADJ)") (class "Default")
      (node (ref "R21") (pin "1") (pinfunction "1_1") (pintype "passive"))
      (node (ref "R22") (pin "2") (pinfunction "2_2") (pintype "passive"))
      (node (ref "U3") (pin "5") (pinfunction "ADJ_5") (pintype "input"))
    )
    (net (code "132") (name "Net-(UEP-WP)") (class "Default")
      (node (ref "R1X") (pin "2") (pinfunction "2_2") (pintype "passive"))
      (node (ref "R2X") (pin "1") (pinfunction "1_1") (pintype "passive"))
      (node (ref "UEP") (pin "7") (pinfunction "WP_7") (pintype "input"))
    )
    (net (code "133") (name "Net-(UNE-VINA+)") (class "Default")
      (node (ref "R7") (pin "2") (pinfunction "2_2") (pintype "passive"))
      (node (ref "R8") (pin "1") (pinfunction "1_1") (pintype "passive"))
      (node (ref "UNE") (pin "3") (pinfunction "VINA+_3") (pintype "input"))
    )
    (net (code "134") (name "Net-(UNE-VINB-)") (class "Default")
      (node (ref "R8") (pin "2") (pinfunction "2_2") (pintype "passive"))
      (node (ref "R9") (pin "1") (pinfunction "1_1") (pintype "passive"))
      (node (ref "UNE") (pin "6") (pinfunction "VINB-_6") (pintype "input"))
    )
    (net (code "135") (name "Net-(UNN-VINA+)") (class "Default")
      (node (ref "R4") (pin "2") (pinfunction "2_2") (pintype "passive"))
      (node (ref "R5") (pin "1") (pinfunction "1_1") (pintype "passive"))
      (node (ref "UNN") (pin "3") (pinfunction "VINA+_3") (pintype "input"))
    )
    (net (code "136") (name "Net-(UNN-VINB-)") (class "Default")
      (node (ref "R5") (pin "2") (pinfunction "2_2") (pintype "passive"))
      (node (ref "R6") (pin "1") (pinfunction "1_1") (pintype "passive"))
      (node (ref "UNN") (pin "6") (pinfunction "VINB-_6") (pintype "input"))
    )
    (net (code "137") (name "Net-(UNW-VINA+)") (class "Default")
      (node (ref "R1") (pin "2") (pinfunction "2_2") (pintype "passive"))
      (node (ref "R2") (pin "1") (pinfunction "1_1") (pintype "passive"))
      (node (ref "UNW") (pin "3") (pinfunction "VINA+_3") (pintype "input"))
    )
    (net (code "138") (name "Net-(UNW-VINB-)") (class "Default")
      (node (ref "R2") (pin "2") (pinfunction "2_2") (pintype "passive"))
      (node (ref "R3") (pin "1") (pinfunction "1_1") (pintype "passive"))
      (node (ref "UNW") (pin "6") (pinfunction "VINB-_6") (pintype "input"))
    )
    (net (code "139") (name "Net-(USE-VINA+)") (class "Default")
      (node (ref "R10") (pin "2") (pinfunction "2_2") (pintype "passive"))
      (node (ref "R11") (pin "1") (pinfunction "1_1") (pintype "passive"))
      (node (ref "USE") (pin "3") (pinfunction "VINA+_3") (pintype "input"))
    )
    (net (code "140") (name "Net-(USE-VINB-)") (class "Default")
      (node (ref "R11") (pin "2") (pinfunction "2_2") (pintype "passive"))
      (node (ref "R12") (pin "1") (pinfunction "1_1") (pintype "passive"))
      (node (ref "USE") (pin "6") (pinfunction "VINB-_6") (pintype "input"))
    )
    (net (code "141") (name "Net-(USS-VINA+)") (class "Default")
      (node (ref "R13") (pin "2") (pinfunction "2_2") (pintype "passive"))
      (node (ref "R14") (pin "1") (pinfunction "1_1") (pintype "passive"))
      (node (ref "USS") (pin "3") (pinfunction "VINA+_3") (pintype "input"))
    )
    (net (code "142") (name "Net-(USS-VINB-)") (class "Default")
      (node (ref "R14") (pin "2") (pinfunction "2_2") (pintype "passive"))
      (node (ref "R15") (pin "1") (pinfunction "1_1") (pintype "passive"))
      (node (ref "USS") (pin "6") (pinfunction "VINB-_6") (pintype "input"))
    )
    (net (code "143") (name "Net-(USW-VINA+)") (class "Default")
      (node (ref "R16") (pin "2") (pinfunction "2_2") (pintype "passive"))
      (node (ref "R17") (pin "1") (pinfunction "1_1") (pintype "passive"))
      (node (ref "USW") (pin "3") (pinfunction "VINA+_3") (pintype "input"))
    )
    (net (code "144") (name "Net-(USW-VINB-)") (class "Default")
      (node (ref "R17") (pin "2") (pinfunction "2_2") (pintype "passive"))
      (node (ref "R18") (pin "1") (pinfunction "1_1") (pintype "passive"))
      (node (ref "USW") (pin "6") (pinfunction "VINB-_6") (pintype "input"))
    )
    (net (code "145") (name "S00_N") (class "Default")
      (node (ref "X-SOUTH") (pin "16") (pinfunction "16_16") (pintype "bidirectional"))
    )
    (net (code "146") (name "S00_P") (class "Default")
      (node (ref "X-SOUTH") (pin "14") (pinfunction "14_14") (pintype "bidirectional"))
    )
    (net (code "147") (name "S01_N") (class "Default")
      (node (ref "X-SOUTH") (pin "17") (pinfunction "17_17") (pintype "bidirectional"))
    )
    (net (code "148") (name "S01_P") (class "Default")
      (node (ref "X-SOUTH") (pin "15") (pinfunction "15_15") (pintype "bidirectional"))
    )
    (net (code "149") (name "S02_N") (class "Default")
      (node (ref "X-SOUTH") (pin "22") (pinfunction "22_22") (pintype "bidirectional"))
    )
    (net (code "150") (name "S02_P") (class "Default")
      (node (ref "X-SOUTH") (pin "20") (pinfunction "20_20") (pintype "bidirectional"))
    )
    (net (code "151") (name "S03_N") (class "Default")
      (node (ref "X-SOUTH") (pin "23") (pinfunction "23_23") (pintype "bidirectional"))
    )
    (net (code "152") (name "S03_P") (class "Default")
      (node (ref "X-SOUTH") (pin "21") (pinfunction "21_21") (pintype "bidirectional"))
    )
    (net (code "153") (name "S04_N") (class "Default")
      (node (ref "SENSOR") (pin "C24") (pinfunction "OUT32_N_C24") (pintype "output"))
      (node (ref "X-SOUTH") (pin "28") (pinfunction "28_28") (pintype "bidirectional"))
    )
    (net (code "154") (name "S04_P") (class "Default")
      (node (ref "SENSOR") (pin "C25") (pinfunction "OUT32_P_C25") (pintype "output"))
      (node (ref "X-SOUTH") (pin "26") (pinfunction "26_26") (pintype "bidirectional"))
    )
    (net (code "155") (name "S05_N") (class "Default")
      (node (ref "X-SOUTH") (pin "29") (pinfunction "29_29") (pintype "bidirectional"))
    )
    (net (code "156") (name "S05_P") (class "Default")
      (node (ref "X-SOUTH") (pin "27") (pinfunction "27_27") (pintype "bidirectional"))
    )
    (net (code "157") (name "S06_N") (class "Default")
      (node (ref "SENSOR") (pin "D23") (pinfunction "OUT30_N_D23") (pintype "output"))
      (node (ref "X-SOUTH") (pin "34") (pinfunction "34_34") (pintype "bidirectional"))
    )
    (net (code "158") (name "S06_P") (class "Default")
      (node (ref "SENSOR") (pin "D24") (pinfunction "OUT30_P_D24") (pintype "output"))
      (node (ref "X-SOUTH") (pin "32") (pinfunction "32_32") (pintype "bidirectional"))
    )
    (net (code "159") (name "S07_N") (class "Default")
      (node (ref "SENSOR") (pin "B24") (pinfunction "OUT31_N_B24") (pintype "output"))
      (node (ref "X-SOUTH") (pin "35") (pinfunction "35_35") (pintype "bidirectional"))
    )
    (net (code "160") (name "S07_P") (class "Default")
      (node (ref "SENSOR") (pin "B25") (pinfunction "OUT31_P_B25") (pintype "output"))
      (node (ref "X-SOUTH") (pin "33") (pinfunction "33_33") (pintype "bidirectional"))
    )
    (net (code "161") (name "S08_N") (class "Default")
      (node (ref "SENSOR") (pin "D21") (pinfunction "OUT27_N_D21") (pintype "output"))
      (node (ref "X-SOUTH") (pin "40") (pinfunction "40_40") (pintype "bidirectional"))
    )
    (net (code "162") (name "S08_P") (class "Default")
      (node (ref "SENSOR") (pin "D22") (pinfunction "OUT27_P_D22") (pintype "output"))
      (node (ref "X-SOUTH") (pin "38") (pinfunction "38_38") (pintype "bidirectional"))
    )
    (net (code "163") (name "S09_N") (class "Default")
      (node (ref "SENSOR") (pin "A23") (pinfunction "OUT29_N_A23") (pintype "output"))
      (node (ref "X-SOUTH") (pin "41") (pinfunction "41_41") (pintype "bidirectional"))
    )
    (net (code "164") (name "S09_P") (class "Default")
      (node (ref "SENSOR") (pin "A24") (pinfunction "OUT29_P_A24") (pintype "output"))
      (node (ref "X-SOUTH") (pin "39") (pinfunction "39_39") (pintype "bidirectional"))
    )
    (net (code "165") (name "S10_N") (class "Default")
      (node (ref "SENSOR") (pin "C21") (pinfunction "OUT28_N_C21") (pintype "output"))
      (node (ref "X-SOUTH") (pin "46") (pinfunction "46_46") (pintype "bidirectional"))
    )
    (net (code "166") (name "S10_P") (class "Default")
      (node (ref "SENSOR") (pin "C22") (pinfunction "OUT28_P_C22") (pintype "output"))
      (node (ref "X-SOUTH") (pin "44") (pinfunction "44_44") (pintype "bidirectional"))
    )
    (net (code "167") (name "S11_N") (class "Default")
      (node (ref "SENSOR") (pin "B20") (pinfunction "OUT26_N_B20") (pintype "output"))
      (node (ref "X-SOUTH") (pin "47") (pinfunction "47_47") (pintype "bidirectional"))
    )
    (net (code "168") (name "S11_P") (class "Default")
      (node (ref "SENSOR") (pin "B21") (pinfunction "OUT26_P_B21") (pintype "output"))
      (node (ref "X-SOUTH") (pin "45") (pinfunction "45_45") (pintype "bidirectional"))
    )
    (net (code "169") (name "S12_N") (class "Default")
      (node (ref "SENSOR") (pin "D19") (pinfunction "OUT24_N_D19") (pintype "output"))
      (node (ref "X-SOUTH") (pin "52") (pinfunction "52_52") (pintype "bidirectional"))
    )
    (net (code "170") (name "S12_P") (class "Default")
      (node (ref "SENSOR") (pin "D20") (pinfunction "OUT24_P_D20") (pintype "output"))
      (node (ref "X-SOUTH") (pin "50") (pinfunction "50_50") (pintype "bidirectional"))
    )
    (net (code "171") (name "S13_N") (class "Default")
      (node (ref "SENSOR") (pin "A19") (pinfunction "OUT23_N_A19") (pintype "output"))
      (node (ref "X-SOUTH") (pin "53") (pinfunction "53_53") (pintype "bidirectional"))
    )
    (net (code "172") (name "S13_P") (class "Default")
      (node (ref "SENSOR") (pin "A20") (pinfunction "OUT23_P_A20") (pintype "output"))
      (node (ref "X-SOUTH") (pin "51") (pinfunction "51_51") (pintype "bidirectional"))
    )
    (net (code "173") (name "S14_N") (class "Default")
      (node (ref "SENSOR") (pin "C19") (pinfunction "OUT25_N_C19") (pintype "output"))
      (node (ref "X-SOUTH") (pin "58") (pinfunction "58_58") (pintype "bidirectional"))
    )
    (net (code "174") (name "S14_P") (class "Default")
      (node (ref "SENSOR") (pin "C20") (pinfunction "OUT25_P_C20") (pintype "output"))
      (node (ref "X-SOUTH") (pin "56") (pinfunction "56_56") (pintype "bidirectional"))
    )
    (net (code "175") (name "S15_N") (class "Default")
      (node (ref "SENSOR") (pin "B18") (pinfunction "OUT22_N_B18") (pintype "output"))
      (node (ref "X-SOUTH") (pin "59") (pinfunction "59_59") (pintype "bidirectional"))
    )
    (net (code "176") (name "S15_P") (class "Default")
      (node (ref "SENSOR") (pin "B19") (pinfunction "OUT22_P_B19") (pintype "output"))
      (node (ref "X-SOUTH") (pin "57") (pinfunction "57_57") (pintype "bidirectional"))
    )
    (net (code "177") (name "S16_N") (class "Default")
      (node (ref "SENSOR") (pin "C17") (pinfunction "OUT21_N_C17") (pintype "output"))
      (node (ref "X-SOUTH") (pin "64") (pinfunction "64_64") (pintype "bidirectional"))
    )
    (net (code "178") (name "S16_P") (class "Default")
      (node (ref "SENSOR") (pin "C18") (pinfunction "OUT21_P_C18") (pintype "output"))
      (node (ref "X-SOUTH") (pin "62") (pinfunction "62_62") (pintype "bidirectional"))
    )
    (net (code "179") (name "S17_N") (class "Default")
      (node (ref "SENSOR") (pin "A17") (pinfunction "OUT19_N_A17") (pintype "output"))
      (node (ref "X-SOUTH") (pin "65") (pinfunction "65_65") (pintype "bidirectional"))
    )
    (net (code "180") (name "S17_P") (class "Default")
      (node (ref "SENSOR") (pin "A18") (pinfunction "OUT19_P_A18") (pintype "output"))
      (node (ref "X-SOUTH") (pin "63") (pinfunction "63_63") (pintype "bidirectional"))
    )
    (net (code "181") (name "S18_N") (class "Default")
      (node (ref "SENSOR") (pin "D17") (pinfunction "OUT20_N_D17") (pintype "output"))
      (node (ref "X-SOUTH") (pin "70") (pinfunction "70_70") (pintype "bidirectional"))
    )
    (net (code "182") (name "S18_P") (class "Default")
      (node (ref "SENSOR") (pin "D18") (pinfunction "OUT20_P_D18") (pintype "output"))
      (node (ref "X-SOUTH") (pin "68") (pinfunction "68_68") (pintype "bidirectional"))
    )
    (net (code "183") (name "S19_N") (class "Default")
      (node (ref "SENSOR") (pin "B16") (pinfunction "OUT18_N_B16") (pintype "output"))
      (node (ref "X-SOUTH") (pin "71") (pinfunction "71_71") (pintype "bidirectional"))
    )
    (net (code "184") (name "S19_P") (class "Default")
      (node (ref "SENSOR") (pin "B17") (pinfunction "OUT18_P_B17") (pintype "output"))
      (node (ref "X-SOUTH") (pin "69") (pinfunction "69_69") (pintype "bidirectional"))
    )
    (net (code "185") (name "S20_N") (class "Default")
      (node (ref "SENSOR") (pin "D15") (pinfunction "OUT17_N_D15") (pintype "output"))
      (node (ref "X-SOUTH") (pin "76") (pinfunction "76_76") (pintype "bidirectional"))
    )
    (net (code "186") (name "S20_P") (class "Default")
      (node (ref "SENSOR") (pin "D16") (pinfunction "OUT17_P_D16") (pintype "output"))
      (node (ref "X-SOUTH") (pin "74") (pinfunction "74_74") (pintype "bidirectional"))
    )
    (net (code "187") (name "S21_N") (class "Default")
      (node (ref "SENSOR") (pin "B14") (pinfunction "OUT16_N_B14") (pintype "output"))
      (node (ref "X-SOUTH") (pin "77") (pinfunction "77_77") (pintype "bidirectional"))
    )
    (net (code "188") (name "S21_P") (class "Default")
      (node (ref "SENSOR") (pin "B15") (pinfunction "OUT16_P_B15") (pintype "output"))
      (node (ref "X-SOUTH") (pin "75") (pinfunction "75_75") (pintype "bidirectional"))
    )
    (net (code "189") (name "S22_N") (class "Default")
      (node (ref "SENSOR") (pin "D13") (pinfunction "OUT15_N_D13") (pintype "output"))
      (node (ref "X-SOUTH") (pin "82") (pinfunction "82_82") (pintype "bidirectional"))
    )
    (net (code "190") (name "S22_P") (class "Default")
      (node (ref "SENSOR") (pin "D14") (pinfunction "OUT15_P_D14") (pintype "output"))
      (node (ref "X-SOUTH") (pin "80") (pinfunction "80_80") (pintype "bidirectional"))
    )
    (net (code "191") (name "S23_N") (class "Default")
      (node (ref "SENSOR") (pin "A13") (pinfunction "OUT13_N_A13") (pintype "output"))
      (node (ref "X-SOUTH") (pin "83") (pinfunction "83_83") (pintype "bidirectional"))
    )
    (net (code "192") (name "S23_P") (class "Default")
      (node (ref "SENSOR") (pin "A14") (pinfunction "OUT13_P_A14") (pintype "output"))
      (node (ref "X-SOUTH") (pin "81") (pinfunction "81_81") (pintype "bidirectional"))
    )
    (net (code "193") (name "S24_N") (class "Default")
      (node (ref "SENSOR") (pin "C13") (pinfunction "OUT14_N_C13") (pintype "output"))
      (node (ref "X-SOUTH") (pin "88") (pinfunction "88_88") (pintype "bidirectional"))
    )
    (net (code "194") (name "S24_P") (class "Default")
      (node (ref "SENSOR") (pin "C14") (pinfunction "OUT14_P_C14") (pintype "output"))
      (node (ref "X-SOUTH") (pin "86") (pinfunction "86_86") (pintype "bidirectional"))
    )
    (net (code "195") (name "S25_N") (class "Default")
      (node (ref "SENSOR") (pin "B12") (pinfunction "OUT12_N_B12") (pintype "output"))
      (node (ref "X-SOUTH") (pin "89") (pinfunction "89_89") (pintype "bidirectional"))
    )
    (net (code "196") (name "S25_P") (class "Default")
      (node (ref "SENSOR") (pin "B13") (pinfunction "OUT12_P_B13") (pintype "output"))
      (node (ref "X-SOUTH") (pin "87") (pinfunction "87_87") (pintype "bidirectional"))
    )
    (net (code "197") (name "S26_N") (class "Default")
      (node (ref "SENSOR") (pin "D11") (pinfunction "OUT10_N_D11") (pintype "output"))
      (node (ref "X-SOUTH") (pin "94") (pinfunction "94_94") (pintype "bidirectional"))
    )
    (net (code "198") (name "S26_P") (class "Default")
      (node (ref "SENSOR") (pin "D12") (pinfunction "OUT10_P_D12") (pintype "output"))
      (node (ref "X-SOUTH") (pin "92") (pinfunction "92_92") (pintype "bidirectional"))
    )
    (net (code "199") (name "S27_N") (class "Default")
      (node (ref "SENSOR") (pin "A11") (pinfunction "OUT9_N_A11") (pintype "output"))
      (node (ref "X-SOUTH") (pin "95") (pinfunction "95_95") (pintype "bidirectional"))
    )
    (net (code "200") (name "S27_P") (class "Default")
      (node (ref "SENSOR") (pin "A12") (pinfunction "OUT9_P_A12") (pintype "output"))
      (node (ref "X-SOUTH") (pin "93") (pinfunction "93_93") (pintype "bidirectional"))
    )
    (net (code "201") (name "S28_N") (class "Default")
      (node (ref "SENSOR") (pin "C11") (pinfunction "OUT11_N_C11") (pintype "output"))
      (node (ref "X-SOUTH") (pin "100") (pinfunction "100_100") (pintype "bidirectional"))
    )
    (net (code "202") (name "S28_P") (class "Default")
      (node (ref "SENSOR") (pin "C12") (pinfunction "OUT11_P_C12") (pintype "output"))
      (node (ref "X-SOUTH") (pin "98") (pinfunction "98_98") (pintype "bidirectional"))
    )
    (net (code "203") (name "S29_N") (class "Default")
      (node (ref "SENSOR") (pin "B10") (pinfunction "OUT8_N_B10") (pintype "output"))
      (node (ref "X-SOUTH") (pin "101") (pinfunction "101_101") (pintype "bidirectional"))
    )
    (net (code "204") (name "S29_P") (class "Default")
      (node (ref "SENSOR") (pin "B11") (pinfunction "OUT8_P_B11") (pintype "output"))
      (node (ref "X-SOUTH") (pin "99") (pinfunction "99_99") (pintype "bidirectional"))
    )
    (net (code "205") (name "S30_N") (class "Default")
      (node (ref "SENSOR") (pin "C9") (pinfunction "OUT7_N_C9") (pintype "output"))
      (node (ref "X-SOUTH") (pin "106") (pinfunction "106_106") (pintype "bidirectional"))
    )
    (net (code "206") (name "S30_P") (class "Default")
      (node (ref "SENSOR") (pin "C10") (pinfunction "OUT7_P_C10") (pintype "output"))
      (node (ref "X-SOUTH") (pin "104") (pinfunction "104_104") (pintype "bidirectional"))
    )
    (net (code "207") (name "S31_N") (class "Default")
      (node (ref "SENSOR") (pin "B8") (pinfunction "OUT5_N_B8") (pintype "output"))
      (node (ref "X-SOUTH") (pin "107") (pinfunction "107_107") (pintype "bidirectional"))
    )
    (net (code "208") (name "S31_P") (class "Default")
      (node (ref "SENSOR") (pin "B9") (pinfunction "OUT5_P_B9") (pintype "output"))
      (node (ref "X-SOUTH") (pin "105") (pinfunction "105_105") (pintype "bidirectional"))
    )
    (net (code "209") (name "S32_N") (class "Default")
      (node (ref "SENSOR") (pin "D9") (pinfunction "OUT6_N_D9") (pintype "output"))
      (node (ref "X-SOUTH") (pin "112") (pinfunction "112_112") (pintype "bidirectional"))
    )
    (net (code "210") (name "S32_P") (class "Default")
      (node (ref "SENSOR") (pin "D10") (pinfunction "OUT6_P_D10") (pintype "output"))
      (node (ref "X-SOUTH") (pin "110") (pinfunction "110_110") (pintype "bidirectional"))
    )
    (net (code "211") (name "S33_N") (class "Default")
      (node (ref "SENSOR") (pin "A7") (pinfunction "OUT2_N_A7") (pintype "output"))
      (node (ref "X-SOUTH") (pin "113") (pinfunction "113_113") (pintype "bidirectional"))
    )
    (net (code "212") (name "S33_P") (class "Default")
      (node (ref "SENSOR") (pin "A8") (pinfunction "OUT2_P_A8") (pintype "output"))
      (node (ref "X-SOUTH") (pin "111") (pinfunction "111_111") (pintype "bidirectional"))
    )
    (net (code "213") (name "S34_N") (class "Default")
      (node (ref "SENSOR") (pin "C7") (pinfunction "OUT4_N_C7") (pintype "output"))
      (node (ref "X-SOUTH") (pin "118") (pinfunction "118_118") (pintype "bidirectional"))
    )
    (net (code "214") (name "S34_P") (class "Default")
      (node (ref "SENSOR") (pin "C8") (pinfunction "OUT4_P_C8") (pintype "output"))
      (node (ref "X-SOUTH") (pin "116") (pinfunction "116_116") (pintype "bidirectional"))
    )
    (net (code "215") (name "S35_N") (class "Default")
      (node (ref "SENSOR") (pin "B6") (pinfunction "OUT1_N_B6") (pintype "output"))
      (node (ref "X-SOUTH") (pin "119") (pinfunction "119_119") (pintype "bidirectional"))
    )
    (net (code "216") (name "S35_P") (class "Default")
      (node (ref "SENSOR") (pin "B7") (pinfunction "OUT1_P_B7") (pintype "output"))
      (node (ref "X-SOUTH") (pin "117") (pinfunction "117_117") (pintype "bidirectional"))
    )
    (net (code "217") (name "S36_N") (class "Default")
      (node (ref "SENSOR") (pin "D7") (pinfunction "OUT3_N_D7") (pintype "output"))
      (node (ref "X-SOUTH") (pin "124") (pinfunction "124_124") (pintype "bidirectional"))
    )
    (net (code "218") (name "S36_P") (class "Default")
      (node (ref "SENSOR") (pin "D8") (pinfunction "OUT3_P_D8") (pintype "output"))
      (node (ref "X-SOUTH") (pin "122") (pinfunction "122_122") (pintype "bidirectional"))
    )
    (net (code "219") (name "S37_N") (class "Default")
      (node (ref "SENSOR") (pin "A5") (pinfunction "OUTCTR_N_A5") (pintype "output"))
      (node (ref "X-SOUTH") (pin "125") (pinfunction "125_125") (pintype "bidirectional"))
    )
    (net (code "220") (name "S37_P") (class "Default")
      (node (ref "SENSOR") (pin "A6") (pinfunction "OUTCTR_P_A6") (pintype "output"))
      (node (ref "X-SOUTH") (pin "123") (pinfunction "123_123") (pintype "bidirectional"))
    )
    (net (code "221") (name "S38_N") (class "Default")
      (node (ref "X-SOUTH") (pin "130") (pinfunction "130_130") (pintype "bidirectional"))
    )
    (net (code "222") (name "S38_P") (class "Default")
      (node (ref "X-SOUTH") (pin "128") (pinfunction "128_128") (pintype "bidirectional"))
    )
    (net (code "223") (name "S39_N") (class "Default")
      (node (ref "U3") (pin "6") (pinfunction "EN_6") (pintype "input"))
      (node (ref "X-SOUTH") (pin "131") (pinfunction "131_131") (pintype "bidirectional"))
    )
    (net (code "224") (name "S39_P") (class "Default")
      (node (ref "X-SOUTH") (pin "129") (pinfunction "129_129") (pintype "bidirectional"))
    )
    (net (code "225") (name "SPI_CLK") (class "Default")
      (node (ref "SENSOR") (pin "H29") (pinfunction "SPI_CLK_H29") (pintype "input"))
      (node (ref "U4") (pin "6") (pinfunction "1A1_6") (pintype "output"))
    )
    (net (code "226") (name "SPI_EN") (class "Default")
      (node (ref "SENSOR") (pin "F28") (pinfunction "SPI_EN_F28") (pintype "input"))
      (node (ref "U6") (pin "9") (pinfunction "B4_9") (pintype "bidirectional"))
    )
    (net (code "227") (name "SPI_IN") (class "Default")
      (node (ref "SENSOR") (pin "E28") (pinfunction "SPI_IN_E28") (pintype "input"))
      (node (ref "U4") (pin "7") (pinfunction "1A2_7") (pintype "output"))
    )
    (net (code "228") (name "SPI_OUT") (class "Default")
      (node (ref "SENSOR") (pin "G28") (pinfunction "SPI_OUT_G28") (pintype "output"))
      (node (ref "U4") (pin "8") (pinfunction "2A1_8") (pintype "output"))
    )
    (net (code "229") (name "SYS_RES_N") (class "Default")
      (node (ref "SENSOR") (pin "F30") (pinfunction "SYS_RES_N_F30") (pintype "input"))
      (node (ref "U5") (pin "10") (pinfunction "B3_10") (pintype "bidirectional"))
    )
    (net (code "230") (name "S_CHK_V") (class "Default")
      (node (ref "C5") (pin "1") (pinfunction "1_1") (pintype "passive"))
      (node (ref "C6") (pin "1") (pinfunction "1_1") (pintype "passive"))
      (node (ref "C7") (pin "1") (pinfunction "1_1") (pintype "passive"))
      (node (ref "R20") (pin "1") (pinfunction "1_1") (pintype "passive"))
      (node (ref "TP3") (pin "TP") (pinfunction "TP_TP") (pintype "input"))
      (node (ref "USE") (pin "8") (pinfunction "VDD_8") (pintype "power_in"))
      (node (ref "USS") (pin "8") (pinfunction "VDD_8") (pintype "power_in"))
      (node (ref "USW") (pin "8") (pinfunction "VDD_8") (pintype "power_in"))
      (node (ref "X-SOUTH") (pin "10") (pinfunction "10_10") (pintype "bidirectional"))
      (node (ref "X-SOUTH") (pin "8") (pinfunction "8_8") (pintype "bidirectional"))
    )
    (net (code "231") (name "S_I2C_V") (class "Default")
      (node (ref "U7") (pin "8") (pinfunction "VCC_8") (pintype "power_in"))
      (node (ref "X-SOUTH") (pin "135") (pinfunction "135_135") (pintype "bidirectional"))
      (node (ref "X-SOUTH") (pin "137") (pinfunction "137_137") (pintype "bidirectional"))
    )
    (net (code "232") (name "S_REF") (class "Default")
      (node (ref "R20") (pin "2") (pinfunction "2_2") (pintype "passive"))
      (node (ref "TP4") (pin "TP") (pinfunction "TP_TP") (pintype "input"))
      (node (ref "U2") (pin "1") (pinfunction "CATHODE_1") (pintype "output"))
      (node (ref "U2") (pin "3") (pinfunction "REF_3") (pintype "input"))
      (node (ref "USE") (pin "2") (pinfunction "VINA-_2") (pintype "input"))
      (node (ref "USE") (pin "5") (pinfunction "VINB+_5") (pintype "input"))
      (node (ref "USS") (pin "2") (pinfunction "VINA-_2") (pintype "input"))
      (node (ref "USS") (pin "5") (pinfunction "VINB+_5") (pintype "input"))
      (node (ref "USW") (pin "2") (pinfunction "VINA-_2") (pintype "input"))
      (node (ref "USW") (pin "5") (pinfunction "VINB+_5") (pintype "input"))
    )
    (net (code "233") (name "S_SCK") (class "Default")
      (node (ref "X-SOUTH") (pin "144") (pinfunction "144_144") (pintype "bidirectional"))
    )
    (net (code "234") (name "S_SCL") (class "Default")
      (node (ref "U7") (pin "2") (pinfunction "SCL_2") (pintype "input"))
      (node (ref "X-SOUTH") (pin "143") (pinfunction "143_143") (pintype "bidirectional"))
    )
    (net (code "235") (name "S_SDA") (class "Default")
      (node (ref "U7") (pin "1") (pinfunction "SDA_1") (pintype "bidirectional"))
      (node (ref "X-SOUTH") (pin "141") (pinfunction "141_141") (pintype "bidirectional"))
    )
    (net (code "236") (name "S_SDI") (class "Default")
      (node (ref "X-SOUTH") (pin "140") (pinfunction "140_140") (pintype "bidirectional"))
    )
    (net (code "237") (name "S_SDO") (class "Default")
      (node (ref "X-SOUTH") (pin "142") (pinfunction "142_142") (pintype "bidirectional"))
    )
    (net (code "238") (name "S_SPI_V") (class "Default")
      (node (ref "X-SOUTH") (pin "134") (pinfunction "134_134") (pintype "bidirectional"))
      (node (ref "X-SOUTH") (pin "136") (pinfunction "136_136") (pintype "bidirectional"))
    )
    (net (code "239") (name "S_VE") (class "Default")
      (node (ref "X-SOUTH") (pin "13") (pinfunction "13_13") (pintype "bidirectional"))
      (node (ref "X-SOUTH") (pin "19") (pinfunction "19_19") (pintype "bidirectional"))
      (node (ref "X-SOUTH") (pin "25") (pinfunction "25_25") (pintype "bidirectional"))
      (node (ref "X-SOUTH") (pin "31") (pinfunction "31_31") (pintype "bidirectional"))
      (node (ref "X-SOUTH") (pin "37") (pinfunction "37_37") (pintype "bidirectional"))
    )
    (net (code "240") (name "S_VE_CV") (class "Default")
      (node (ref "C11") (pin "1") (pinfunction "1_1") (pintype "passive"))
      (node (ref "R10") (pin "1") (pinfunction "1_1") (pintype "passive"))
      (node (ref "X-SOUTH") (pin "2") (pinfunction "2_2") (pintype "bidirectional"))
    )
    (net (code "241") (name "S_VE_OV") (class "Default")
      (node (ref "USE") (pin "7") (pinfunction "OUTB_7") (pintype "output"))
      (node (ref "X-SOUTH") (pin "1") (pinfunction "1_1") (pintype "bidirectional"))
    )
    (net (code "242") (name "S_VE_UV") (class "Default")
      (node (ref "USE") (pin "1") (pinfunction "OUTA_1") (pintype "output"))
      (node (ref "X-SOUTH") (pin "7") (pinfunction "7_7") (pintype "bidirectional"))
    )
    (net (code "243") (name "S_VS") (class "Default")
      (node (ref "C45") (pin "1") (pinfunction "1_1") (pintype "passive"))
      (node (ref "C46") (pin "1") (pinfunction "1_1") (pintype "passive"))
      (node (ref "C47") (pin "1") (pinfunction "1_1") (pintype "passive"))
      (node (ref "C48") (pin "1") (pinfunction "1_1") (pintype "passive"))
      (node (ref "C49") (pin "1") (pinfunction "1_1") (pintype "passive"))
      (node (ref "C72") (pin "1") (pinfunction "1_1") (pintype "passive"))
      (node (ref "C73") (pin "1") (pinfunction "1_1") (pintype "passive"))
      (node (ref "C74") (pin "1") (pinfunction "1_1") (pintype "passive"))
      (node (ref "C81") (pin "1") (pinfunction "1_1") (pintype "passive"))
      (node (ref "C82") (pin "1") (pinfunction "1_1") (pintype "passive"))
      (node (ref "C83") (pin "1") (pinfunction "1_1") (pintype "passive"))
      (node (ref "SENSOR") (pin "A30") (pinfunction "VDD_PIX_A30") (pintype "power_in"))
      (node (ref "SENSOR") (pin "D28") (pinfunction "VDD_PIX_D28") (pintype "power_in"))
      (node (ref "SENSOR") (pin "D30") (pinfunction "VDD_PIX_D30") (pintype "power_in"))
      (node (ref "SENSOR") (pin "G1") (pinfunction "VDD_PIX_G1") (pintype "power_in"))
      (node (ref "SENSOR") (pin "H28") (pinfunction "VDD_PIX_H28") (pintype "power_in"))
      (node (ref "TP6") (pin "TP") (pinfunction "TP_TP") (pintype "input"))
      (node (ref "X-SOUTH") (pin "49") (pinfunction "49_49") (pintype "bidirectional"))
      (node (ref "X-SOUTH") (pin "55") (pinfunction "55_55") (pintype "bidirectional"))
      (node (ref "X-SOUTH") (pin "61") (pinfunction "61_61") (pintype "bidirectional"))
      (node (ref "X-SOUTH") (pin "67") (pinfunction "67_67") (pintype "bidirectional"))
      (node (ref "X-SOUTH") (pin "73") (pinfunction "73_73") (pintype "bidirectional"))
      (node (ref "X-SOUTH") (pin "79") (pinfunction "79_79") (pintype "bidirectional"))
      (node (ref "X-SOUTH") (pin "85") (pinfunction "85_85") (pintype "bidirectional"))
      (node (ref "X-SOUTH") (pin "91") (pinfunction "91_91") (pintype "bidirectional"))
      (node (ref "X-SOUTH") (pin "97") (pinfunction "97_97") (pintype "bidirectional"))
    )
    (net (code "244") (name "S_VS_CV") (class "Default")
      (node (ref "C12") (pin "1") (pinfunction "1_1") (pintype "passive"))
      (node (ref "R13") (pin "1") (pinfunction "1_1") (pintype "passive"))
      (node (ref "X-SOUTH") (pin "4") (pinfunction "4_4") (pintype "bidirectional"))
    )
    (net (code "245") (name "S_VS_OV") (class "Default")
      (node (ref "USS") (pin "7") (pinfunction "OUTB_7") (pintype "output"))
      (node (ref "X-SOUTH") (pin "3") (pinfunction "3_3") (pintype "bidirectional"))
    )
    (net (code "246") (name "S_VS_UV") (class "Default")
      (node (ref "USS") (pin "1") (pinfunction "OUTA_1") (pintype "output"))
      (node (ref "X-SOUTH") (pin "9") (pinfunction "9_9") (pintype "bidirectional"))
    )
    (net (code "247") (name "S_VW") (class "Default")
      (node (ref "C90") (pin "1") (pinfunction "1_1") (pintype "passive"))
      (node (ref "U3") (pin "1") (pinfunction "BIAS_1") (pintype "power_in"))
      (node (ref "U3") (pin "3") (pinfunction "IN_3") (pintype "power_in"))
      (node (ref "X-SOUTH") (pin "109") (pinfunction "109_109") (pintype "bidirectional"))
      (node (ref "X-SOUTH") (pin "115") (pinfunction "115_115") (pintype "bidirectional"))
      (node (ref "X-SOUTH") (pin "121") (pinfunction "121_121") (pintype "bidirectional"))
      (node (ref "X-SOUTH") (pin "127") (pinfunction "127_127") (pintype "bidirectional"))
      (node (ref "X-SOUTH") (pin "133") (pinfunction "133_133") (pintype "bidirectional"))
    )
    (net (code "248") (name "S_VW_CV") (class "Default")
      (node (ref "C13") (pin "1") (pinfunction "1_1") (pintype "passive"))
      (node (ref "R16") (pin "1") (pinfunction "1_1") (pintype "passive"))
      (node (ref "X-SOUTH") (pin "6") (pinfunction "6_6") (pintype "bidirectional"))
    )
    (net (code "249") (name "S_VW_OV") (class "Default")
      (node (ref "USW") (pin "7") (pinfunction "OUTB_7") (pintype "output"))
      (node (ref "X-SOUTH") (pin "5") (pinfunction "5_5") (pintype "bidirectional"))
    )
    (net (code "250") (name "S_VW_UV") (class "Default")
      (node (ref "USW") (pin "1") (pinfunction "OUTA_1") (pintype "output"))
      (node (ref "X-SOUTH") (pin "11") (pinfunction "11_11") (pintype "bidirectional"))
    )
    (net (code "251") (name "TDIG1") (class "Default")
      (node (ref "SENSOR") (pin "G27") (pinfunction "TDIG1_G27") (pintype "output"))
      (node (ref "U5") (pin "9") (pinfunction "B4_9") (pintype "bidirectional"))
    )
    (net (code "252") (name "TDIG2") (class "Default")
      (node (ref "SENSOR") (pin "G26") (pinfunction "TDIG2_G26") (pintype "output"))
      (node (ref "U6") (pin "11") (pinfunction "B2_11") (pintype "bidirectional"))
    )
    (net (code "253") (name "T_EXP1") (class "Default")
      (node (ref "SENSOR") (pin "H30") (pinfunction "T_EXP1_H30") (pintype "input"))
      (node (ref "U5") (pin "12") (pinfunction "B1_12") (pintype "bidirectional"))
    )
    (net (code "254") (name "T_EXP2") (class "Default")
      (node (ref "SENSOR") (pin "E29") (pinfunction "T_EXP2_E29") (pintype "input"))
      (node (ref "U6") (pin "10") (pinfunction "B3_10") (pintype "bidirectional"))
    )
    (net (code "255") (name "VRAMP1") (class "Default")
      (node (ref "C16") (pin "1") (pinfunction "1_1") (pintype "passive"))
      (node (ref "R23") (pin "1") (pinfunction "1_1") (pintype "passive"))
      (node (ref "SENSOR") (pin "G29") (pinfunction "VRAMP1_G29") (pintype "bidirectional"))
    )
    (net (code "256") (name "VRAMP2") (class "Default")
      (node (ref "C17") (pin "1") (pinfunction "1_1") (pintype "passive"))
      (node (ref "R23") (pin "2") (pinfunction "2_2") (pintype "passive"))
      (node (ref "SENSOR") (pin "F29") (pinfunction "VRAMP2_F29") (pintype "bidirectional"))
    )
    (net (code "257") (name "VTREF") (class "Default")
      (node (ref "C65") (pin "1") (pinfunction "1_1") (pintype "passive"))
      (node (ref "C91") (pin "2") (pinfunction "2_2") (pintype "passive"))
      (node (ref "R21") (pin "2") (pinfunction "2_2") (pintype "passive"))
      (node (ref "R24") (pin "1") (pinfunction "1_1") (pintype "passive"))
      (node (ref "SENSOR") (pin "B2") (pinfunction "VTREF_B2") (pintype "bidirectional"))
      (node (ref "U3") (pin "4") (pinfunction "OUT_4") (pintype "power_in"))
    )
    (net (code "258") (name "VTSIG") (class "Default")
      (node (ref "C66") (pin "1") (pinfunction "1_1") (pintype "passive"))
      (node (ref "R24") (pin "2") (pinfunction "2_2") (pintype "passive"))
      (node (ref "SENSOR") (pin "C2") (pinfunction "VTSIG_C2") (pintype "bidirectional"))
    )
    (net (code "259") (name "unconnected-(U1-NC-Pad2)") (class "Default")
      (node (ref "U1") (pin "2") (pinfunction "NC_2") (pintype "no_connect"))
    )
    (net (code "260") (name "unconnected-(U1-NC-Pad4)") (class "Default")
      (node (ref "U1") (pin "4") (pinfunction "NC_4") (pintype "no_connect"))
    )
    (net (code "261") (name "unconnected-(U1-NC-Pad5)") (class "Default")
      (node (ref "U1") (pin "5") (pinfunction "NC_5") (pintype "no_connect"))
    )
    (net (code "262") (name "unconnected-(U2-NC-Pad2)") (class "Default")
      (node (ref "U2") (pin "2") (pinfunction "NC_2") (pintype "no_connect"))
    )
    (net (code "263") (name "unconnected-(U2-NC-Pad4)") (class "Default")
      (node (ref "U2") (pin "4") (pinfunction "NC_4") (pintype "no_connect"))
    )
    (net (code "264") (name "unconnected-(U2-NC-Pad5)") (class "Default")
      (node (ref "U2") (pin "5") (pinfunction "NC_5") (pintype "no_connect"))
    )
    (net (code "265") (name "unconnected-(U4-2B2-Pad12)") (class "Default")
      (node (ref "U4") (pin "12") (pinfunction "2B2_12") (pintype "output"))
    )
    (net (code "266") (name "unconnected-(U7-OS-Pad3)") (class "Default")
      (node (ref "U7") (pin "3") (pinfunction "OS_3") (pintype "output"))
    )
    (net (code "267") (name "unconnected-(X-NORTH-PadM1)") (class "Default")
      (node (ref "X-NORTH") (pin "M1") (pinfunction "M1_M1") (pintype "bidirectional"))
    )
    (net (code "268") (name "unconnected-(X-NORTH-PadM2)") (class "Default")
      (node (ref "X-NORTH") (pin "M2") (pinfunction "M2_M2") (pintype "bidirectional"))
    )
    (net (code "269") (name "unconnected-(X-SOUTH-PadM1)") (class "Default")
      (node (ref "X-SOUTH") (pin "M1") (pinfunction "M1_M1") (pintype "bidirectional"))
    )
    (net (code "270") (name "unconnected-(X-SOUTH-PadM2)") (class "Default")
      (node (ref "X-SOUTH") (pin "M2") (pinfunction "M2_M2") (pintype "bidirectional"))
    )
  )
)
